# FPGA.net
KiCad netlist of a schematic drawn in Altium Designer
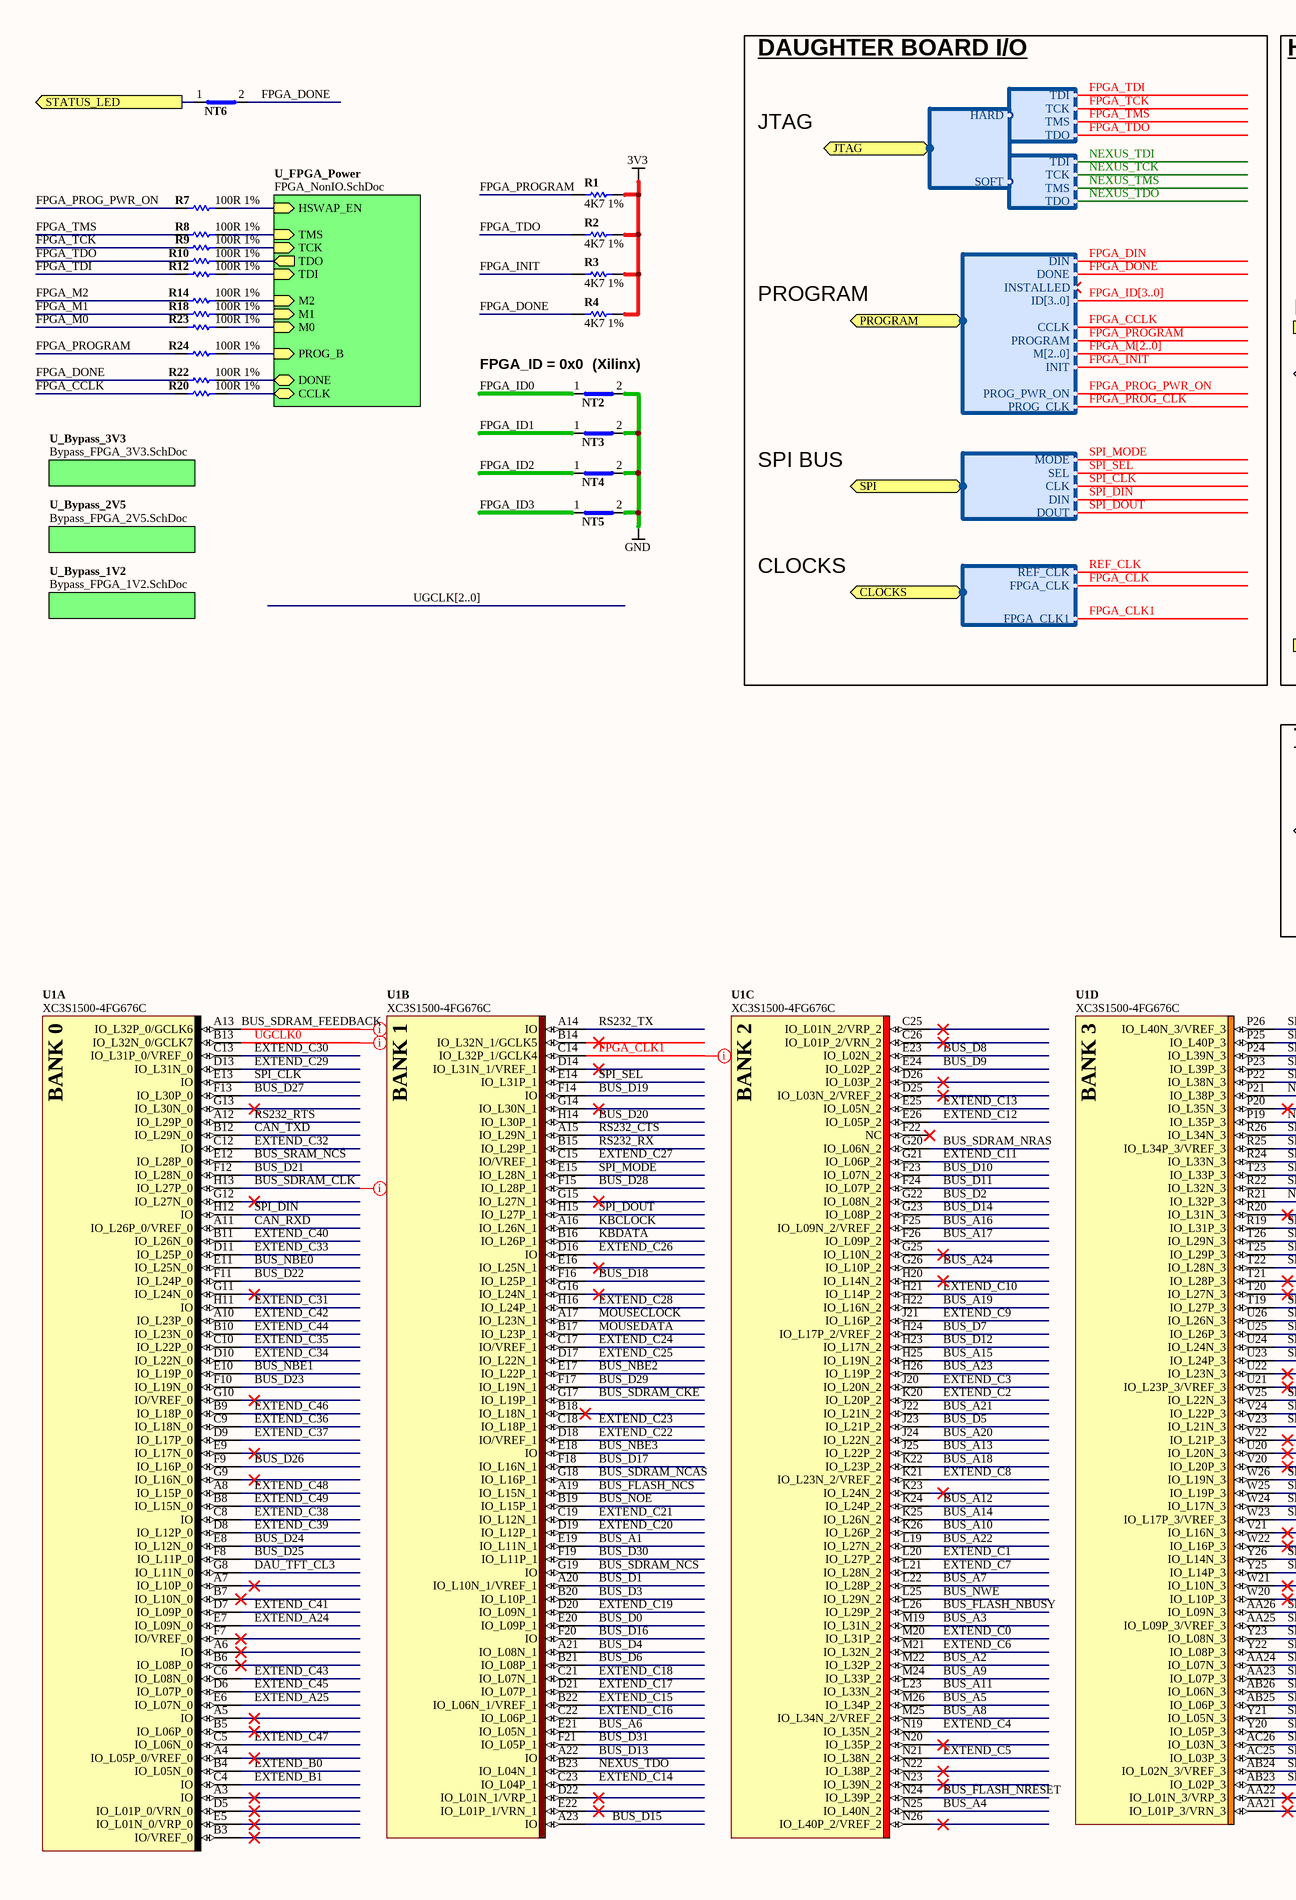
[diagram p0: FPGA.SCHDOC, left]
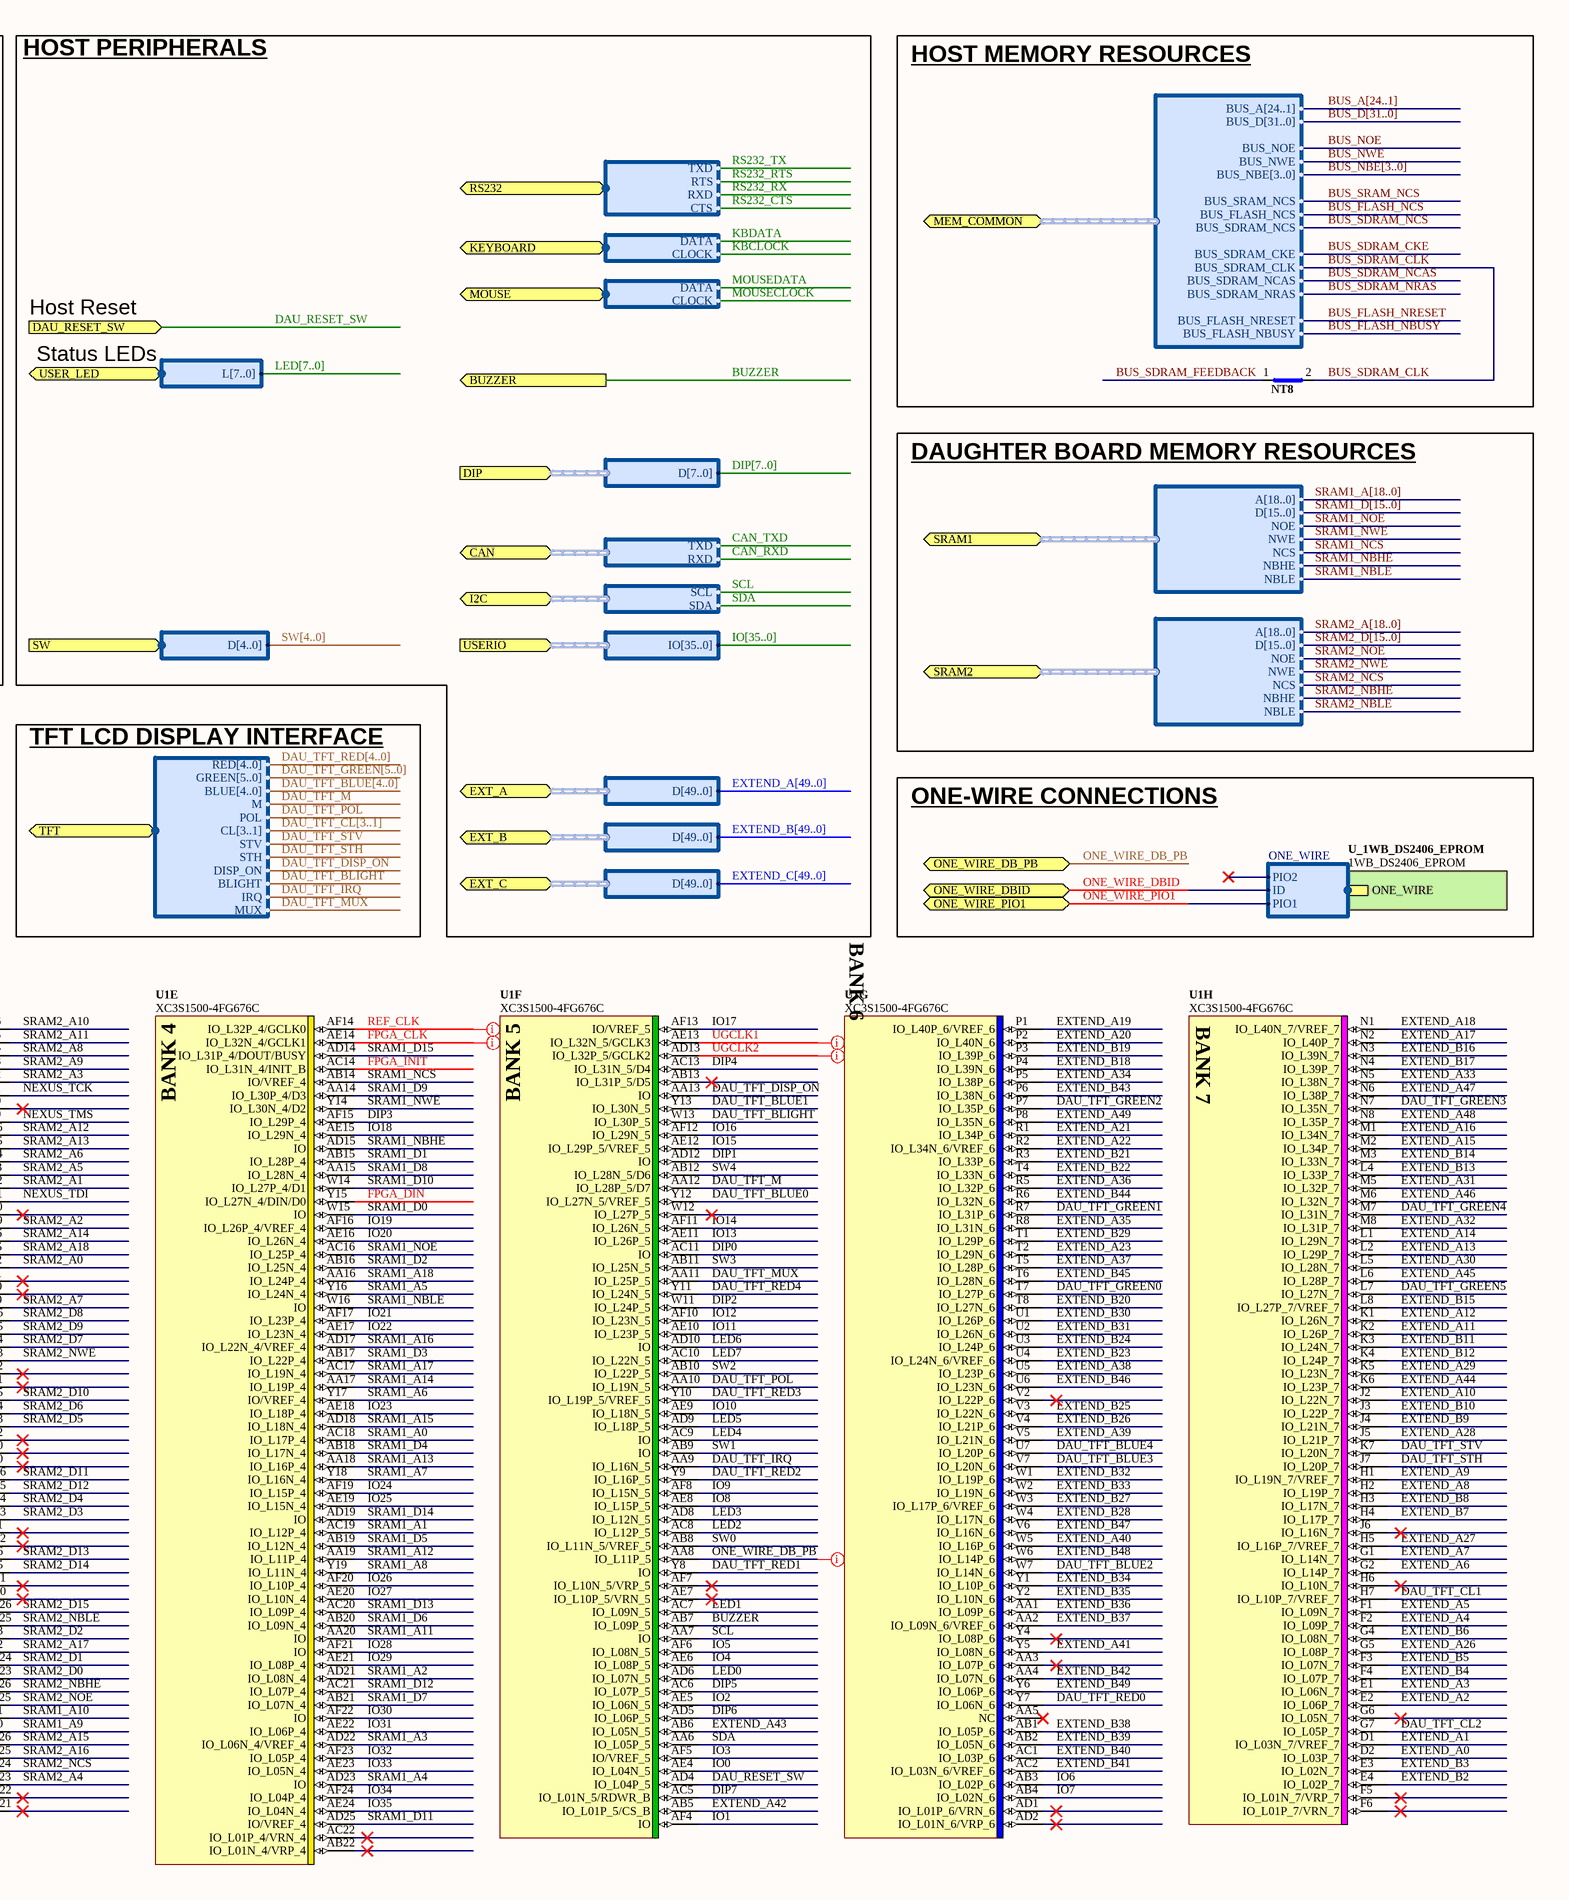
[diagram p1: FPGA.SCHDOC, right]

(export (version "E")
  (design (tool "Eeschema 10.0.6"))
  (components
    (comp (ref "NT2")
      (value "Net Tie SMT2")
      (footprint "NETTIE-SMT2-8X8")
      (description "Net-Tie, Surface Mount, 2 x 0.4mm x 0.2mm SMT Pads - For 0.2mm Track")
      (libsource (lib "AltiumDesignLibrary") (part "NETTIE-SMT2"))
    )
    (comp (ref "NT3")
      (value "Net Tie SMT2")
      (footprint "NETTIE-SMT2-8X8")
      (description "Net-Tie, Surface Mount, 2 x 0.4mm x 0.2mm SMT Pads - For 0.2mm Track")
      (libsource (lib "AltiumDesignLibrary") (part "NETTIE-SMT2"))
    )
    (comp (ref "NT4")
      (value "Net Tie SMT2")
      (footprint "NETTIE-SMT2-8X8")
      (description "Net-Tie, Surface Mount, 2 x 0.4mm x 0.2mm SMT Pads - For 0.2mm Track")
      (libsource (lib "AltiumDesignLibrary") (part "NETTIE-SMT2"))
    )
    (comp (ref "NT5")
      (value "Net Tie SMT2")
      (footprint "NETTIE-SMT2-8X8")
      (description "Net-Tie, Surface Mount, 2 x 0.4mm x 0.2mm SMT Pads - For 0.2mm Track")
      (libsource (lib "AltiumDesignLibrary") (part "NETTIE-SMT2"))
    )
    (comp (ref "NT6")
      (value "Net Tie SMT2")
      (footprint "NETTIE-SMT2-8X8")
      (description "Net-Tie, Surface Mount, 2 x 0.4mm x 0.2mm SMT Pads - For 0.2mm Track")
      (libsource (lib "AltiumDesignLibrary") (part "NETTIE-SMT2"))
    )
    (comp (ref "NT8")
      (value "Net Tie SMT2")
      (footprint "NETTIE-SMT2-8X8")
      (description "Net-Tie, Surface Mount, 2 x 0.4mm x 0.2mm SMT Pads - For 0.2mm Track")
      (libsource (lib "AltiumDesignLibrary") (part "NETTIE-SMT2"))
    )
    (comp (ref "R1")
      (value "4K7 1%")
      (footprint "RESC1005-STAR")
      (description "Resistor, 4K7 1% 0402 (1005)")
      (fields (field (name "TOLERANCE") "1 %"))
      (libsource (lib "AltiumDesignLibrary") (part "RES"))
    )
    (comp (ref "R2")
      (value "4K7 1%")
      (footprint "RESC1005-STAR")
      (description "Resistor, 4K7 1% 0402 (1005)")
      (fields (field (name "TOLERANCE") "1 %"))
      (libsource (lib "AltiumDesignLibrary") (part "RES"))
    )
    (comp (ref "R3")
      (value "4K7 1%")
      (footprint "RESC1005-STAR")
      (description "Resistor, 4K7 1% 0402 (1005)")
      (fields (field (name "TOLERANCE") "1 %"))
      (libsource (lib "AltiumDesignLibrary") (part "RES"))
    )
    (comp (ref "R4")
      (value "4K7 1%")
      (footprint "RESC1005-STAR")
      (description "Resistor, 4K7 1% 0402 (1005)")
      (fields (field (name "TOLERANCE") "1 %"))
      (libsource (lib "AltiumDesignLibrary") (part "RES"))
    )
    (comp (ref "R7")
      (value "100R 1%")
      (footprint "RESC1005-STAR")
      (description "Resistor, 100R 1% 0402 (1005)")
      (fields (field (name "TOLERANCE") "1 %"))
      (libsource (lib "AltiumDesignLibrary") (part "RES"))
    )
    (comp (ref "R8")
      (value "100R 1%")
      (footprint "RESC1005-STAR")
      (description "Resistor, 100R 1% 0402 (1005)")
      (fields (field (name "TOLERANCE") "1 %"))
      (libsource (lib "AltiumDesignLibrary") (part "RES"))
    )
    (comp (ref "R9")
      (value "100R 1%")
      (footprint "RESC1005-STAR")
      (description "Resistor, 100R 1% 0402 (1005)")
      (fields (field (name "TOLERANCE") "1 %"))
      (libsource (lib "AltiumDesignLibrary") (part "RES"))
    )
    (comp (ref "R10")
      (value "100R 1%")
      (footprint "RESC1005-STAR")
      (description "Resistor, 100R 1% 0402 (1005)")
      (fields (field (name "TOLERANCE") "1 %"))
      (libsource (lib "AltiumDesignLibrary") (part "RES"))
    )
    (comp (ref "R12")
      (value "100R 1%")
      (footprint "RESC1005-STAR")
      (description "Resistor, 100R 1% 0402 (1005)")
      (fields (field (name "TOLERANCE") "1 %"))
      (libsource (lib "AltiumDesignLibrary") (part "RES"))
    )
    (comp (ref "R14")
      (value "100R 1%")
      (footprint "RESC1005-STAR")
      (description "Resistor, 100R 1% 0402 (1005)")
      (fields (field (name "TOLERANCE") "1 %"))
      (libsource (lib "AltiumDesignLibrary") (part "RES"))
    )
    (comp (ref "R18")
      (value "100R 1%")
      (footprint "RESC1005-STAR")
      (description "Resistor, 100R 1% 0402 (1005)")
      (fields (field (name "TOLERANCE") "1 %"))
      (libsource (lib "AltiumDesignLibrary") (part "RES"))
    )
    (comp (ref "R20")
      (value "100R 1%")
      (footprint "RESC1005-STAR")
      (description "Resistor, 100R 1% 0402 (1005)")
      (fields (field (name "TOLERANCE") "1 %"))
      (libsource (lib "AltiumDesignLibrary") (part "RES"))
    )
    (comp (ref "R22")
      (value "100R 1%")
      (footprint "RESC1005-STAR")
      (description "Resistor, 100R 1% 0402 (1005)")
      (fields (field (name "TOLERANCE") "1 %"))
      (libsource (lib "AltiumDesignLibrary") (part "RES"))
    )
    (comp (ref "R23")
      (value "100R 1%")
      (footprint "RESC1005-STAR")
      (description "Resistor, 100R 1% 0402 (1005)")
      (fields (field (name "TOLERANCE") "1 %"))
      (libsource (lib "AltiumDesignLibrary") (part "RES"))
    )
    (comp (ref "R24")
      (value "100R 1%")
      (footprint "RESC1005-STAR")
      (description "Resistor, 100R 1% 0402 (1005)")
      (fields (field (name "TOLERANCE") "1 %"))
      (libsource (lib "AltiumDesignLibrary") (part "RES"))
    )
    (comp (ref "U1")
      (value "XC3S1500-4FG676C")
      (footprint "BGA100P26X26-676")
      (description "FPGA, Xilinx Spartan3-1500 FG676 Speed=4")
      (libsource (lib "AltiumDesignLibrary") (part "XC3S1500-4FG676C"))
    )
  )
  (nets
    (net (code "18") (name "/BUS_A1") (class "Default")
      (node (ref "U1") (pin "E19") (pinfunction "IO_L11N_1_E19") (pintype "bidirectional"))
    )
    (net (code "19") (name "/BUS_A2") (class "Default")
      (node (ref "U1") (pin "M22") (pinfunction "IO_L32P_2_M22") (pintype "bidirectional"))
    )
    (net (code "20") (name "/BUS_A3") (class "Default")
      (node (ref "U1") (pin "M19") (pinfunction "IO_L31N_2_M19") (pintype "bidirectional"))
    )
    (net (code "21") (name "/BUS_A4") (class "Default")
      (node (ref "U1") (pin "N25") (pinfunction "IO_L40N_2_N25") (pintype "bidirectional"))
    )
    (net (code "22") (name "/BUS_A5") (class "Default")
      (node (ref "U1") (pin "M26") (pinfunction "IO_L34P_2_M26") (pintype "bidirectional"))
    )
    (net (code "23") (name "/BUS_A6") (class "Default")
      (node (ref "U1") (pin "E21") (pinfunction "IO_L05N_1_E21") (pintype "bidirectional"))
    )
    (net (code "24") (name "/BUS_A7") (class "Default")
      (node (ref "U1") (pin "L22") (pinfunction "IO_L28P_2_L22") (pintype "bidirectional"))
    )
    (net (code "25") (name "/BUS_A8") (class "Default")
      (node (ref "U1") (pin "M25") (pinfunction "IO_L34N_2/VREF_2_M25") (pintype "bidirectional"))
    )
    (net (code "26") (name "/BUS_A9") (class "Default")
      (node (ref "U1") (pin "M24") (pinfunction "IO_L33P_2_M24") (pintype "bidirectional"))
    )
    (net (code "27") (name "/BUS_A10") (class "Default")
      (node (ref "U1") (pin "K26") (pinfunction "IO_L26P_2_K26") (pintype "bidirectional"))
    )
    (net (code "28") (name "/BUS_A11") (class "Default")
      (node (ref "U1") (pin "L23") (pinfunction "IO_L33N_2_L23") (pintype "bidirectional"))
    )
    (net (code "29") (name "/BUS_A12") (class "Default")
      (node (ref "U1") (pin "K24") (pinfunction "IO_L24P_2_K24") (pintype "bidirectional"))
    )
    (net (code "30") (name "/BUS_A13") (class "Default")
      (node (ref "U1") (pin "J25") (pinfunction "IO_L22P_2_J25") (pintype "bidirectional"))
    )
    (net (code "31") (name "/BUS_A14") (class "Default")
      (node (ref "U1") (pin "K25") (pinfunction "IO_L26N_2_K25") (pintype "bidirectional"))
    )
    (net (code "32") (name "/BUS_A15") (class "Default")
      (node (ref "U1") (pin "H25") (pinfunction "IO_L19N_2_H25") (pintype "bidirectional"))
    )
    (net (code "33") (name "/BUS_A16") (class "Default")
      (node (ref "U1") (pin "F25") (pinfunction "IO_L09N_2/VREF_2_F25") (pintype "bidirectional"))
    )
    (net (code "34") (name "/BUS_A17") (class "Default")
      (node (ref "U1") (pin "F26") (pinfunction "IO_L09P_2_F26") (pintype "bidirectional"))
    )
    (net (code "35") (name "/BUS_A18") (class "Default")
      (node (ref "U1") (pin "K22") (pinfunction "IO_L23P_2_K22") (pintype "bidirectional"))
    )
    (net (code "36") (name "/BUS_A19") (class "Default")
      (node (ref "U1") (pin "H22") (pinfunction "IO_L16N_2_H22") (pintype "bidirectional"))
    )
    (net (code "37") (name "/BUS_A20") (class "Default")
      (node (ref "U1") (pin "J24") (pinfunction "IO_L22N_2_J24") (pintype "bidirectional"))
    )
    (net (code "38") (name "/BUS_A21") (class "Default")
      (node (ref "U1") (pin "J22") (pinfunction "IO_L21N_2_J22") (pintype "bidirectional"))
    )
    (net (code "39") (name "/BUS_A22") (class "Default")
      (node (ref "U1") (pin "L19") (pinfunction "IO_L27N_2_L19") (pintype "bidirectional"))
    )
    (net (code "40") (name "/BUS_A23") (class "Default")
      (node (ref "U1") (pin "H26") (pinfunction "IO_L19P_2_H26") (pintype "bidirectional"))
    )
    (net (code "41") (name "/BUS_A24") (class "Default")
      (node (ref "U1") (pin "G26") (pinfunction "IO_L10P_2_G26") (pintype "bidirectional"))
    )
    (net (code "43") (name "/BUS_D0") (class "Default")
      (node (ref "U1") (pin "E20") (pinfunction "IO_L09P_1_E20") (pintype "bidirectional"))
    )
    (net (code "44") (name "/BUS_D1") (class "Default")
      (node (ref "U1") (pin "A20") (pinfunction "IO_L10N_1/VREF_1_A20") (pintype "bidirectional"))
    )
    (net (code "45") (name "/BUS_D2") (class "Default")
      (node (ref "U1") (pin "G22") (pinfunction "IO_L08N_2_G22") (pintype "bidirectional"))
    )
    (net (code "46") (name "/BUS_D3") (class "Default")
      (node (ref "U1") (pin "B20") (pinfunction "IO_L10P_1_B20") (pintype "bidirectional"))
    )
    (net (code "47") (name "/BUS_D4") (class "Default")
      (node (ref "U1") (pin "A21") (pinfunction "IO_L08N_1_A21") (pintype "bidirectional"))
    )
    (net (code "48") (name "/BUS_D5") (class "Default")
      (node (ref "U1") (pin "J23") (pinfunction "IO_L21P_2_J23") (pintype "bidirectional"))
    )
    (net (code "49") (name "/BUS_D6") (class "Default")
      (node (ref "U1") (pin "B21") (pinfunction "IO_L08P_1_B21") (pintype "bidirectional"))
    )
    (net (code "50") (name "/BUS_D7") (class "Default")
      (node (ref "U1") (pin "H24") (pinfunction "IO_L17P_2/VREF_2_H24") (pintype "bidirectional"))
    )
    (net (code "51") (name "/BUS_D8") (class "Default")
      (node (ref "U1") (pin "E23") (pinfunction "IO_L02N_2_E23") (pintype "bidirectional"))
    )
    (net (code "52") (name "/BUS_D9") (class "Default")
      (node (ref "U1") (pin "E24") (pinfunction "IO_L02P_2_E24") (pintype "bidirectional"))
    )
    (net (code "53") (name "/BUS_D10") (class "Default")
      (node (ref "U1") (pin "F23") (pinfunction "IO_L07N_2_F23") (pintype "bidirectional"))
    )
    (net (code "54") (name "/BUS_D11") (class "Default")
      (node (ref "U1") (pin "F24") (pinfunction "IO_L07P_2_F24") (pintype "bidirectional"))
    )
    (net (code "55") (name "/BUS_D12") (class "Default")
      (node (ref "U1") (pin "H23") (pinfunction "IO_L17N_2_H23") (pintype "bidirectional"))
    )
    (net (code "56") (name "/BUS_D13") (class "Default")
      (node (ref "U1") (pin "A22") (pinfunction "IO_A22") (pintype "bidirectional"))
    )
    (net (code "57") (name "/BUS_D14") (class "Default")
      (node (ref "U1") (pin "G23") (pinfunction "IO_L08P_2_G23") (pintype "bidirectional"))
    )
    (net (code "58") (name "/BUS_D15") (class "Default")
      (node (ref "U1") (pin "A23") (pinfunction "IO_A23") (pintype "bidirectional"))
    )
    (net (code "59") (name "/BUS_D16") (class "Default")
      (node (ref "U1") (pin "F20") (pinfunction "IO_F20") (pintype "bidirectional"))
    )
    (net (code "60") (name "/BUS_D17") (class "Default")
      (node (ref "U1") (pin "F18") (pinfunction "IO_L16N_1_F18") (pintype "bidirectional"))
    )
    (net (code "61") (name "/BUS_D18") (class "Default")
      (node (ref "U1") (pin "F16") (pinfunction "IO_L25P_1_F16") (pintype "bidirectional"))
    )
    (net (code "62") (name "/BUS_D19") (class "Default")
      (node (ref "U1") (pin "F14") (pinfunction "IO_F14") (pintype "bidirectional"))
    )
    (net (code "63") (name "/BUS_D20") (class "Default")
      (node (ref "U1") (pin "H14") (pinfunction "IO_L30P_1_H14") (pintype "bidirectional"))
    )
    (net (code "64") (name "/BUS_D21") (class "Default")
      (node (ref "U1") (pin "F12") (pinfunction "IO_L28N_0_F12") (pintype "bidirectional"))
    )
    (net (code "65") (name "/BUS_D22") (class "Default")
      (node (ref "U1") (pin "F11") (pinfunction "IO_L24P_0_F11") (pintype "bidirectional"))
    )
    (net (code "66") (name "/BUS_D23") (class "Default")
      (node (ref "U1") (pin "F10") (pinfunction "IO_L19N_0_F10") (pintype "bidirectional"))
    )
    (net (code "67") (name "/BUS_D24") (class "Default")
      (node (ref "U1") (pin "E8") (pinfunction "IO_L12N_0_E8") (pintype "bidirectional"))
    )
    (net (code "68") (name "/BUS_D25") (class "Default")
      (node (ref "U1") (pin "F8") (pinfunction "IO_L11P_0_F8") (pintype "bidirectional"))
    )
    (net (code "69") (name "/BUS_D26") (class "Default")
      (node (ref "U1") (pin "F9") (pinfunction "IO_L16P_0_F9") (pintype "bidirectional"))
    )
    (net (code "70") (name "/BUS_D27") (class "Default")
      (node (ref "U1") (pin "F13") (pinfunction "IO_L30P_0_F13") (pintype "bidirectional"))
    )
    (net (code "71") (name "/BUS_D28") (class "Default")
      (node (ref "U1") (pin "F15") (pinfunction "IO_L28P_1_F15") (pintype "bidirectional"))
    )
    (net (code "72") (name "/BUS_D29") (class "Default")
      (node (ref "U1") (pin "F17") (pinfunction "IO_L19N_1_F17") (pintype "bidirectional"))
    )
    (net (code "73") (name "/BUS_D30") (class "Default")
      (node (ref "U1") (pin "F19") (pinfunction "IO_L11P_1_F19") (pintype "bidirectional"))
    )
    (net (code "74") (name "/BUS_D31") (class "Default")
      (node (ref "U1") (pin "F21") (pinfunction "IO_L05P_1_F21") (pintype "bidirectional"))
    )
    (net (code "76") (name "/BUS_FLASH_NBUSY") (class "Default")
      (node (ref "U1") (pin "L26") (pinfunction "IO_L29P_2_L26") (pintype "bidirectional"))
    )
    (net (code "77") (name "/BUS_FLASH_NCS") (class "Default")
      (node (ref "U1") (pin "A19") (pinfunction "IO_L15N_1_A19") (pintype "bidirectional"))
    )
    (net (code "78") (name "/BUS_FLASH_NRESET") (class "Default")
      (node (ref "U1") (pin "N24") (pinfunction "IO_L39P_2_N24") (pintype "bidirectional"))
    )
    (net (code "79") (name "/BUS_NBE0") (class "Default")
      (node (ref "U1") (pin "E11") (pinfunction "IO_L25N_0_E11") (pintype "bidirectional"))
    )
    (net (code "80") (name "/BUS_NBE1") (class "Default")
      (node (ref "U1") (pin "E10") (pinfunction "IO_L19P_0_E10") (pintype "bidirectional"))
    )
    (net (code "81") (name "/BUS_NBE2") (class "Default")
      (node (ref "U1") (pin "E17") (pinfunction "IO_L22P_1_E17") (pintype "bidirectional"))
    )
    (net (code "82") (name "/BUS_NBE3") (class "Default")
      (node (ref "U1") (pin "E18") (pinfunction "IO_E18") (pintype "bidirectional"))
    )
    (net (code "84") (name "/BUS_NOE") (class "Default")
      (node (ref "U1") (pin "B19") (pinfunction "IO_L15P_1_B19") (pintype "bidirectional"))
    )
    (net (code "85") (name "/BUS_NWE") (class "Default")
      (node (ref "U1") (pin "L25") (pinfunction "IO_L29N_2_L25") (pintype "bidirectional"))
    )
    (net (code "86") (name "/BUS_SDRAM_CKE") (class "Default")
      (node (ref "U1") (pin "G17") (pinfunction "IO_L19P_1_G17") (pintype "bidirectional"))
    )
    (net (code "87") (name "/BUS_SDRAM_CLK") (class "Default")
      (node (ref "NT8") (pin "2") (pinfunction "Net2_2") (pintype "passive"))
      (node (ref "U1") (pin "H13") (pinfunction "IO_L27P_0_H13") (pintype "bidirectional"))
    )
    (net (code "88") (name "/BUS_SDRAM_FEEDBACK") (class "Default")
      (node (ref "NT8") (pin "1") (pinfunction "Net1_1") (pintype "passive"))
      (node (ref "U1") (pin "A13") (pinfunction "IO_L32P_0/GCLK6_A13") (pintype "bidirectional"))
    )
    (net (code "89") (name "/BUS_SDRAM_NCAS") (class "Default")
      (node (ref "U1") (pin "G18") (pinfunction "IO_L16P_1_G18") (pintype "bidirectional"))
    )
    (net (code "90") (name "/BUS_SDRAM_NCS") (class "Default")
      (node (ref "U1") (pin "G19") (pinfunction "IO_G19") (pintype "bidirectional"))
    )
    (net (code "91") (name "/BUS_SDRAM_NRAS") (class "Default")
      (node (ref "U1") (pin "G20") (pinfunction "IO_L06N_2_G20") (pintype "bidirectional"))
    )
    (net (code "92") (name "/BUS_SRAM_NCS") (class "Default")
      (node (ref "U1") (pin "E12") (pinfunction "IO_L28P_0_E12") (pintype "bidirectional"))
    )
    (net (code "93") (name "/BUZZER") (class "Default")
      (node (ref "U1") (pin "AB7") (pinfunction "IO_L09P_5_AB7") (pintype "bidirectional"))
    )
    (net (code "94") (name "/CAN_RXD") (class "Default")
      (node (ref "U1") (pin "A11") (pinfunction "IO_L26P_0/VREF_0_A11") (pintype "bidirectional"))
    )
    (net (code "95") (name "/CAN_TXD") (class "Default")
      (node (ref "U1") (pin "B12") (pinfunction "IO_L29N_0_B12") (pintype "bidirectional"))
    )
    (net (code "96") (name "/CCLK") (class "Default")
      (node (ref "R20") (pin "2") (pinfunction "2_2") (pintype "passive"))
    )
    (net (code "97") (name "/DAU_RESET_SW") (class "Default")
      (node (ref "U1") (pin "AD4") (pinfunction "IO_L04P_5_AD4") (pintype "bidirectional"))
    )
    (net (code "98") (name "/DAU_TFT_BLIGHT") (class "Default")
      (node (ref "U1") (pin "W13") (pinfunction "IO_L30P_5_W13") (pintype "bidirectional"))
    )
    (net (code "99") (name "/DAU_TFT_BLUE0") (class "Default")
      (node (ref "U1") (pin "Y12") (pinfunction "IO_L27N_5/VREF_5_Y12") (pintype "bidirectional"))
    )
    (net (code "100") (name "/DAU_TFT_BLUE1") (class "Default")
      (node (ref "U1") (pin "Y13") (pinfunction "IO_L30N_5_Y13") (pintype "bidirectional"))
    )
    (net (code "101") (name "/DAU_TFT_BLUE2") (class "Default")
      (node (ref "U1") (pin "W7") (pinfunction "IO_L14N_6_W7") (pintype "bidirectional"))
    )
    (net (code "102") (name "/DAU_TFT_BLUE3") (class "Default")
      (node (ref "U1") (pin "V7") (pinfunction "IO_L20N_6_V7") (pintype "bidirectional"))
    )
    (net (code "103") (name "/DAU_TFT_BLUE4") (class "Default")
      (node (ref "U1") (pin "U7") (pinfunction "IO_L20P_6_U7") (pintype "bidirectional"))
    )
    (net (code "105") (name "/DAU_TFT_CL1") (class "Default")
      (node (ref "U1") (pin "H7") (pinfunction "IO_L10P_7/VREF_7_H7") (pintype "bidirectional"))
    )
    (net (code "106") (name "/DAU_TFT_CL2") (class "Default")
      (node (ref "U1") (pin "G7") (pinfunction "IO_L05P_7_G7") (pintype "bidirectional"))
    )
    (net (code "107") (name "/DAU_TFT_CL3") (class "Default")
      (node (ref "U1") (pin "G8") (pinfunction "IO_L11N_0_G8") (pintype "bidirectional"))
    )
    (net (code "108") (name "/DAU_TFT_DISP_ON") (class "Default")
      (node (ref "U1") (pin "AA13") (pinfunction "IO_AA13") (pintype "bidirectional"))
    )
    (net (code "109") (name "/DAU_TFT_GREEN0") (class "Default")
      (node (ref "U1") (pin "T7") (pinfunction "IO_L27P_6_T7") (pintype "bidirectional"))
    )
    (net (code "110") (name "/DAU_TFT_GREEN1") (class "Default")
      (node (ref "U1") (pin "R7") (pinfunction "IO_L31P_6_R7") (pintype "bidirectional"))
    )
    (net (code "111") (name "/DAU_TFT_GREEN2") (class "Default")
      (node (ref "U1") (pin "P7") (pinfunction "IO_L35P_6_P7") (pintype "bidirectional"))
    )
    (net (code "112") (name "/DAU_TFT_GREEN3") (class "Default")
      (node (ref "U1") (pin "N7") (pinfunction "IO_L35N_7_N7") (pintype "bidirectional"))
    )
    (net (code "113") (name "/DAU_TFT_GREEN4") (class "Default")
      (node (ref "U1") (pin "M7") (pinfunction "IO_L31N_7_M7") (pintype "bidirectional"))
    )
    (net (code "114") (name "/DAU_TFT_GREEN5") (class "Default")
      (node (ref "U1") (pin "L7") (pinfunction "IO_L27N_7_L7") (pintype "bidirectional"))
    )
    (net (code "116") (name "/DAU_TFT_IRQ") (class "Default")
      (node (ref "U1") (pin "AA9") (pinfunction "IO_L16N_5_AA9") (pintype "bidirectional"))
    )
    (net (code "117") (name "/DAU_TFT_M") (class "Default")
      (node (ref "U1") (pin "AA12") (pinfunction "IO_L28P_5/D7_AA12") (pintype "bidirectional"))
    )
    (net (code "118") (name "/DAU_TFT_MUX") (class "Default")
      (node (ref "U1") (pin "AA11") (pinfunction "IO_L25P_5_AA11") (pintype "bidirectional"))
    )
    (net (code "119") (name "/DAU_TFT_POL") (class "Default")
      (node (ref "U1") (pin "AA10") (pinfunction "IO_L19N_5_AA10") (pintype "bidirectional"))
    )
    (net (code "120") (name "/DAU_TFT_RED0") (class "Default")
      (node (ref "U1") (pin "Y7") (pinfunction "IO_L06N_6_Y7") (pintype "bidirectional"))
    )
    (net (code "121") (name "/DAU_TFT_RED1") (class "Default")
      (node (ref "U1") (pin "Y8") (pinfunction "IO_Y8") (pintype "bidirectional"))
    )
    (net (code "122") (name "/DAU_TFT_RED2") (class "Default")
      (node (ref "U1") (pin "Y9") (pinfunction "IO_L16P_5_Y9") (pintype "bidirectional"))
    )
    (net (code "123") (name "/DAU_TFT_RED3") (class "Default")
      (node (ref "U1") (pin "Y10") (pinfunction "IO_L19P_5/VREF_5_Y10") (pintype "bidirectional"))
    )
    (net (code "124") (name "/DAU_TFT_RED4") (class "Default")
      (node (ref "U1") (pin "Y11") (pinfunction "IO_L24N_5_Y11") (pintype "bidirectional"))
    )
    (net (code "126") (name "/DAU_TFT_STH") (class "Default")
      (node (ref "U1") (pin "J7") (pinfunction "IO_L20P_7_J7") (pintype "bidirectional"))
    )
    (net (code "127") (name "/DAU_TFT_STV") (class "Default")
      (node (ref "U1") (pin "K7") (pinfunction "IO_L20N_7_K7") (pintype "bidirectional"))
    )
    (net (code "128") (name "/DIP0") (class "Default")
      (node (ref "U1") (pin "AC11") (pinfunction "IO_AC11") (pintype "bidirectional"))
    )
    (net (code "129") (name "/DIP1") (class "Default")
      (node (ref "U1") (pin "AD12") (pinfunction "IO_AD12") (pintype "bidirectional"))
    )
    (net (code "130") (name "/DIP2") (class "Default")
      (node (ref "U1") (pin "W11") (pinfunction "IO_L24P_5_W11") (pintype "bidirectional"))
    )
    (net (code "131") (name "/DIP3") (class "Default")
      (node (ref "U1") (pin "AF15") (pinfunction "IO_L29P_4_AF15") (pintype "bidirectional"))
    )
    (net (code "132") (name "/DIP4") (class "Default")
      (node (ref "U1") (pin "AC13") (pinfunction "IO_L31N_5/D4_AC13") (pintype "bidirectional"))
    )
    (net (code "133") (name "/DIP5") (class "Default")
      (node (ref "U1") (pin "AC6") (pinfunction "IO_L07P_5_AC6") (pintype "bidirectional"))
    )
    (net (code "134") (name "/DIP6") (class "Default")
      (node (ref "U1") (pin "AD5") (pinfunction "IO_L06P_5_AD5") (pintype "bidirectional"))
    )
    (net (code "135") (name "/DIP7") (class "Default")
      (node (ref "U1") (pin "AC5") (pinfunction "IO_L01N_5/RDWR_B_AC5") (pintype "bidirectional"))
    )
    (net (code "137") (name "/DONE") (class "Default")
      (node (ref "R22") (pin "2") (pinfunction "2_2") (pintype "passive"))
    )
    (net (code "138") (name "/EXTEND_A0") (class "Default")
      (node (ref "U1") (pin "D2") (pinfunction "IO_L03P_7_D2") (pintype "bidirectional"))
    )
    (net (code "139") (name "/EXTEND_A1") (class "Default")
      (node (ref "U1") (pin "D1") (pinfunction "IO_L03N_7/VREF_7_D1") (pintype "bidirectional"))
    )
    (net (code "140") (name "/EXTEND_A2") (class "Default")
      (node (ref "U1") (pin "E2") (pinfunction "IO_L06P_7_E2") (pintype "bidirectional"))
    )
    (net (code "141") (name "/EXTEND_A3") (class "Default")
      (node (ref "U1") (pin "E1") (pinfunction "IO_L06N_7_E1") (pintype "bidirectional"))
    )
    (net (code "142") (name "/EXTEND_A4") (class "Default")
      (node (ref "U1") (pin "F2") (pinfunction "IO_L09P_7_F2") (pintype "bidirectional"))
    )
    (net (code "143") (name "/EXTEND_A5") (class "Default")
      (node (ref "U1") (pin "F1") (pinfunction "IO_L09N_7_F1") (pintype "bidirectional"))
    )
    (net (code "144") (name "/EXTEND_A6") (class "Default")
      (node (ref "U1") (pin "G2") (pinfunction "IO_L14P_7_G2") (pintype "bidirectional"))
    )
    (net (code "145") (name "/EXTEND_A7") (class "Default")
      (node (ref "U1") (pin "G1") (pinfunction "IO_L14N_7_G1") (pintype "bidirectional"))
    )
    (net (code "146") (name "/EXTEND_A8") (class "Default")
      (node (ref "U1") (pin "H2") (pinfunction "IO_L19P_7_H2") (pintype "bidirectional"))
    )
    (net (code "147") (name "/EXTEND_A9") (class "Default")
      (node (ref "U1") (pin "H1") (pinfunction "IO_L19N_7/VREF_7_H1") (pintype "bidirectional"))
    )
    (net (code "148") (name "/EXTEND_A10") (class "Default")
      (node (ref "U1") (pin "J2") (pinfunction "IO_L22N_7_J2") (pintype "bidirectional"))
    )
    (net (code "149") (name "/EXTEND_A11") (class "Default")
      (node (ref "U1") (pin "K2") (pinfunction "IO_L26P_7_K2") (pintype "bidirectional"))
    )
    (net (code "150") (name "/EXTEND_A12") (class "Default")
      (node (ref "U1") (pin "K1") (pinfunction "IO_L26N_7_K1") (pintype "bidirectional"))
    )
    (net (code "151") (name "/EXTEND_A13") (class "Default")
      (node (ref "U1") (pin "L2") (pinfunction "IO_L29P_7_L2") (pintype "bidirectional"))
    )
    (net (code "152") (name "/EXTEND_A14") (class "Default")
      (node (ref "U1") (pin "L1") (pinfunction "IO_L29N_7_L1") (pintype "bidirectional"))
    )
    (net (code "153") (name "/EXTEND_A15") (class "Default")
      (node (ref "U1") (pin "M2") (pinfunction "IO_L34P_7_M2") (pintype "bidirectional"))
    )
    (net (code "154") (name "/EXTEND_A16") (class "Default")
      (node (ref "U1") (pin "M1") (pinfunction "IO_L34N_7_M1") (pintype "bidirectional"))
    )
    (net (code "155") (name "/EXTEND_A17") (class "Default")
      (node (ref "U1") (pin "N2") (pinfunction "IO_L40P_7_N2") (pintype "bidirectional"))
    )
    (net (code "156") (name "/EXTEND_A18") (class "Default")
      (node (ref "U1") (pin "N1") (pinfunction "IO_L40N_7/VREF_7_N1") (pintype "bidirectional"))
    )
    (net (code "157") (name "/EXTEND_A19") (class "Default")
      (node (ref "U1") (pin "P1") (pinfunction "IO_L40P_6/VREF_6_P1") (pintype "bidirectional"))
    )
    (net (code "158") (name "/EXTEND_A20") (class "Default")
      (node (ref "U1") (pin "P2") (pinfunction "IO_L40N_6_P2") (pintype "bidirectional"))
    )
    (net (code "159") (name "/EXTEND_A21") (class "Default")
      (node (ref "U1") (pin "R1") (pinfunction "IO_L34P_6_R1") (pintype "bidirectional"))
    )
    (net (code "160") (name "/EXTEND_A22") (class "Default")
      (node (ref "U1") (pin "R2") (pinfunction "IO_L34N_6/VREF_6_R2") (pintype "bidirectional"))
    )
    (net (code "161") (name "/EXTEND_A23") (class "Default")
      (node (ref "U1") (pin "T2") (pinfunction "IO_L29N_6_T2") (pintype "bidirectional"))
    )
    (net (code "162") (name "/EXTEND_A24") (class "Default")
      (node (ref "U1") (pin "E7") (pinfunction "IO_L09N_0_E7") (pintype "bidirectional"))
    )
    (net (code "163") (name "/EXTEND_A25") (class "Default")
      (node (ref "U1") (pin "E6") (pinfunction "IO_L07N_0_E6") (pintype "bidirectional"))
    )
    (net (code "164") (name "/EXTEND_A26") (class "Default")
      (node (ref "U1") (pin "G5") (pinfunction "IO_L08P_7_G5") (pintype "bidirectional"))
    )
    (net (code "165") (name "/EXTEND_A27") (class "Default")
      (node (ref "U1") (pin "H5") (pinfunction "IO_L16P_7/VREF_7_H5") (pintype "bidirectional"))
    )
    (net (code "166") (name "/EXTEND_A28") (class "Default")
      (node (ref "U1") (pin "J5") (pinfunction "IO_L21P_7_J5") (pintype "bidirectional"))
    )
    (net (code "167") (name "/EXTEND_A29") (class "Default")
      (node (ref "U1") (pin "K5") (pinfunction "IO_L23N_7_K5") (pintype "bidirectional"))
    )
    (net (code "168") (name "/EXTEND_A30") (class "Default")
      (node (ref "U1") (pin "L5") (pinfunction "IO_L28N_7_L5") (pintype "bidirectional"))
    )
    (net (code "169") (name "/EXTEND_A31") (class "Default")
      (node (ref "U1") (pin "M5") (pinfunction "IO_L32P_7_M5") (pintype "bidirectional"))
    )
    (net (code "170") (name "/EXTEND_A32") (class "Default")
      (node (ref "U1") (pin "M8") (pinfunction "IO_L31P_7_M8") (pintype "bidirectional"))
    )
    (net (code "171") (name "/EXTEND_A33") (class "Default")
      (node (ref "U1") (pin "N5") (pinfunction "IO_L38N_7_N5") (pintype "bidirectional"))
    )
    (net (code "172") (name "/EXTEND_A34") (class "Default")
      (node (ref "U1") (pin "P5") (pinfunction "IO_L38P_6_P5") (pintype "bidirectional"))
    )
    (net (code "173") (name "/EXTEND_A35") (class "Default")
      (node (ref "U1") (pin "R8") (pinfunction "IO_L31N_6_R8") (pintype "bidirectional"))
    )
    (net (code "174") (name "/EXTEND_A36") (class "Default")
      (node (ref "U1") (pin "R5") (pinfunction "IO_L32P_6_R5") (pintype "bidirectional"))
    )
    (net (code "175") (name "/EXTEND_A37") (class "Default")
      (node (ref "U1") (pin "T5") (pinfunction "IO_L28P_6_T5") (pintype "bidirectional"))
    )
    (net (code "176") (name "/EXTEND_A38") (class "Default")
      (node (ref "U1") (pin "U5") (pinfunction "IO_L23P_6_U5") (pintype "bidirectional"))
    )
    (net (code "177") (name "/EXTEND_A39") (class "Default")
      (node (ref "U1") (pin "V5") (pinfunction "IO_L21N_6_V5") (pintype "bidirectional"))
    )
    (net (code "178") (name "/EXTEND_A40") (class "Default")
      (node (ref "U1") (pin "W5") (pinfunction "IO_L16P_6_W5") (pintype "bidirectional"))
    )
    (net (code "179") (name "/EXTEND_A41") (class "Default")
      (node (ref "U1") (pin "Y5") (pinfunction "IO_L08N_6_Y5") (pintype "bidirectional"))
    )
    (net (code "180") (name "/EXTEND_A42") (class "Default")
      (node (ref "U1") (pin "AB5") (pinfunction "IO_L01P_5/CS_B_AB5") (pintype "bidirectional"))
    )
    (net (code "181") (name "/EXTEND_A43") (class "Default")
      (node (ref "U1") (pin "AB6") (pinfunction "IO_L05N_5_AB6") (pintype "bidirectional"))
    )
    (net (code "182") (name "/EXTEND_A44") (class "Default")
      (node (ref "U1") (pin "K6") (pinfunction "IO_L23P_7_K6") (pintype "bidirectional"))
    )
    (net (code "183") (name "/EXTEND_A45") (class "Default")
      (node (ref "U1") (pin "L6") (pinfunction "IO_L28P_7_L6") (pintype "bidirectional"))
    )
    (net (code "184") (name "/EXTEND_A46") (class "Default")
      (node (ref "U1") (pin "M6") (pinfunction "IO_L32N_7_M6") (pintype "bidirectional"))
    )
    (net (code "185") (name "/EXTEND_A47") (class "Default")
      (node (ref "U1") (pin "N6") (pinfunction "IO_L38P_7_N6") (pintype "bidirectional"))
    )
    (net (code "186") (name "/EXTEND_A48") (class "Default")
      (node (ref "U1") (pin "N8") (pinfunction "IO_L35P_7_N8") (pintype "bidirectional"))
    )
    (net (code "187") (name "/EXTEND_A49") (class "Default")
      (node (ref "U1") (pin "P8") (pinfunction "IO_L35N_6_P8") (pintype "bidirectional"))
    )
    (net (code "189") (name "/EXTEND_B0") (class "Default")
      (node (ref "U1") (pin "B4") (pinfunction "IO_L05N_0_B4") (pintype "bidirectional"))
    )
    (net (code "190") (name "/EXTEND_B1") (class "Default")
      (node (ref "U1") (pin "C4") (pinfunction "IO_C4") (pintype "bidirectional"))
    )
    (net (code "191") (name "/EXTEND_B2") (class "Default")
      (node (ref "U1") (pin "E4") (pinfunction "IO_L02P_7_E4") (pintype "bidirectional"))
    )
    (net (code "192") (name "/EXTEND_B3") (class "Default")
      (node (ref "U1") (pin "E3") (pinfunction "IO_L02N_7_E3") (pintype "bidirectional"))
    )
    (net (code "193") (name "/EXTEND_B4") (class "Default")
      (node (ref "U1") (pin "F4") (pinfunction "IO_L07P_7_F4") (pintype "bidirectional"))
    )
    (net (code "194") (name "/EXTEND_B5") (class "Default")
      (node (ref "U1") (pin "F3") (pinfunction "IO_L07N_7_F3") (pintype "bidirectional"))
    )
    (net (code "195") (name "/EXTEND_B6") (class "Default")
      (node (ref "U1") (pin "G4") (pinfunction "IO_L08N_7_G4") (pintype "bidirectional"))
    )
    (net (code "196") (name "/EXTEND_B7") (class "Default")
      (node (ref "U1") (pin "H4") (pinfunction "IO_L17P_7_H4") (pintype "bidirectional"))
    )
    (net (code "197") (name "/EXTEND_B8") (class "Default")
      (node (ref "U1") (pin "H3") (pinfunction "IO_L17N_7_H3") (pintype "bidirectional"))
    )
    (net (code "198") (name "/EXTEND_B9") (class "Default")
      (node (ref "U1") (pin "J4") (pinfunction "IO_L21N_7_J4") (pintype "bidirectional"))
    )
    (net (code "199") (name "/EXTEND_B10") (class "Default")
      (node (ref "U1") (pin "J3") (pinfunction "IO_L22P_7_J3") (pintype "bidirectional"))
    )
    (net (code "200") (name "/EXTEND_B11") (class "Default")
      (node (ref "U1") (pin "K3") (pinfunction "IO_L24N_7_K3") (pintype "bidirectional"))
    )
    (net (code "201") (name "/EXTEND_B12") (class "Default")
      (node (ref "U1") (pin "K4") (pinfunction "IO_L24P_7_K4") (pintype "bidirectional"))
    )
    (net (code "202") (name "/EXTEND_B13") (class "Default")
      (node (ref "U1") (pin "L4") (pinfunction "IO_L33P_7_L4") (pintype "bidirectional"))
    )
    (net (code "203") (name "/EXTEND_B14") (class "Default")
      (node (ref "U1") (pin "M3") (pinfunction "IO_L33N_7_M3") (pintype "bidirectional"))
    )
    (net (code "204") (name "/EXTEND_B15") (class "Default")
      (node (ref "U1") (pin "L8") (pinfunction "IO_L27P_7/VREF_7_L8") (pintype "bidirectional"))
    )
    (net (code "205") (name "/EXTEND_B16") (class "Default")
      (node (ref "U1") (pin "N3") (pinfunction "IO_L39N_7_N3") (pintype "bidirectional"))
    )
    (net (code "206") (name "/EXTEND_B17") (class "Default")
      (node (ref "U1") (pin "N4") (pinfunction "IO_L39P_7_N4") (pintype "bidirectional"))
    )
    (net (code "207") (name "/EXTEND_B18") (class "Default")
      (node (ref "U1") (pin "P4") (pinfunction "IO_L39N_6_P4") (pintype "bidirectional"))
    )
    (net (code "208") (name "/EXTEND_B19") (class "Default")
      (node (ref "U1") (pin "P3") (pinfunction "IO_L39P_6_P3") (pintype "bidirectional"))
    )
    (net (code "209") (name "/EXTEND_B20") (class "Default")
      (node (ref "U1") (pin "T8") (pinfunction "IO_L27N_6_T8") (pintype "bidirectional"))
    )
    (net (code "210") (name "/EXTEND_B21") (class "Default")
      (node (ref "U1") (pin "R3") (pinfunction "IO_L33P_6_R3") (pintype "bidirectional"))
    )
    (net (code "211") (name "/EXTEND_B22") (class "Default")
      (node (ref "U1") (pin "T4") (pinfunction "IO_L33N_6_T4") (pintype "bidirectional"))
    )
    (net (code "212") (name "/EXTEND_B23") (class "Default")
      (node (ref "U1") (pin "U4") (pinfunction "IO_L24N_6/VREF_6_U4") (pintype "bidirectional"))
    )
    (net (code "213") (name "/EXTEND_B24") (class "Default")
      (node (ref "U1") (pin "U3") (pinfunction "IO_L24P_6_U3") (pintype "bidirectional"))
    )
    (net (code "214") (name "/EXTEND_B25") (class "Default")
      (node (ref "U1") (pin "V3") (pinfunction "IO_L22N_6_V3") (pintype "bidirectional"))
    )
    (net (code "215") (name "/EXTEND_B26") (class "Default")
      (node (ref "U1") (pin "V4") (pinfunction "IO_L21P_6_V4") (pintype "bidirectional"))
    )
    (net (code "216") (name "/EXTEND_B27") (class "Default")
      (node (ref "U1") (pin "W3") (pinfunction "IO_L17P_6/VREF_6_W3") (pintype "bidirectional"))
    )
    (net (code "217") (name "/EXTEND_B28") (class "Default")
      (node (ref "U1") (pin "W4") (pinfunction "IO_L17N_6_W4") (pintype "bidirectional"))
    )
    (net (code "218") (name "/EXTEND_B29") (class "Default")
      (node (ref "U1") (pin "T1") (pinfunction "IO_L29P_6_T1") (pintype "bidirectional"))
    )
    (net (code "219") (name "/EXTEND_B30") (class "Default")
      (node (ref "U1") (pin "U1") (pinfunction "IO_L26P_6_U1") (pintype "bidirectional"))
    )
    (net (code "220") (name "/EXTEND_B31") (class "Default")
      (node (ref "U1") (pin "U2") (pinfunction "IO_L26N_6_U2") (pintype "bidirectional"))
    )
    (net (code "221") (name "/EXTEND_B32") (class "Default")
      (node (ref "U1") (pin "W1") (pinfunction "IO_L19P_6_W1") (pintype "bidirectional"))
    )
    (net (code "222") (name "/EXTEND_B33") (class "Default")
      (node (ref "U1") (pin "W2") (pinfunction "IO_L19N_6_W2") (pintype "bidirectional"))
    )
    (net (code "223") (name "/EXTEND_B34") (class "Default")
      (node (ref "U1") (pin "Y1") (pinfunction "IO_L10P_6_Y1") (pintype "bidirectional"))
    )
    (net (code "224") (name "/EXTEND_B35") (class "Default")
      (node (ref "U1") (pin "Y2") (pinfunction "IO_L10N_6_Y2") (pintype "bidirectional"))
    )
    (net (code "225") (name "/EXTEND_B36") (class "Default")
      (node (ref "U1") (pin "AA1") (pinfunction "IO_L09P_6_AA1") (pintype "bidirectional"))
    )
    (net (code "226") (name "/EXTEND_B37") (class "Default")
      (node (ref "U1") (pin "AA2") (pinfunction "IO_L09N_6/VREF_6_AA2") (pintype "bidirectional"))
    )
    (net (code "227") (name "/EXTEND_B38") (class "Default")
      (node (ref "U1") (pin "AB1") (pinfunction "IO_L05P_6_AB1") (pintype "bidirectional"))
    )
    (net (code "228") (name "/EXTEND_B39") (class "Default")
      (node (ref "U1") (pin "AB2") (pinfunction "IO_L05N_6_AB2") (pintype "bidirectional"))
    )
    (net (code "229") (name "/EXTEND_B40") (class "Default")
      (node (ref "U1") (pin "AC1") (pinfunction "IO_L03P_6_AC1") (pintype "bidirectional"))
    )
    (net (code "230") (name "/EXTEND_B41") (class "Default")
      (node (ref "U1") (pin "AC2") (pinfunction "IO_L03N_6/VREF_6_AC2") (pintype "bidirectional"))
    )
    (net (code "231") (name "/EXTEND_B42") (class "Default")
      (node (ref "U1") (pin "AA4") (pinfunction "IO_L07N_6_AA4") (pintype "bidirectional"))
    )
    (net (code "232") (name "/EXTEND_B43") (class "Default")
      (node (ref "U1") (pin "P6") (pinfunction "IO_L38N_6_P6") (pintype "bidirectional"))
    )
    (net (code "233") (name "/EXTEND_B44") (class "Default")
      (node (ref "U1") (pin "R6") (pinfunction "IO_L32N_6_R6") (pintype "bidirectional"))
    )
    (net (code "234") (name "/EXTEND_B45") (class "Default")
      (node (ref "U1") (pin "T6") (pinfunction "IO_L28N_6_T6") (pintype "bidirectional"))
    )
    (net (code "235") (name "/EXTEND_B46") (class "Default")
      (node (ref "U1") (pin "U6") (pinfunction "IO_L23N_6_U6") (pintype "bidirectional"))
    )
    (net (code "236") (name "/EXTEND_B47") (class "Default")
      (node (ref "U1") (pin "V6") (pinfunction "IO_L16N_6_V6") (pintype "bidirectional"))
    )
    (net (code "237") (name "/EXTEND_B48") (class "Default")
      (node (ref "U1") (pin "W6") (pinfunction "IO_L14P_6_W6") (pintype "bidirectional"))
    )
    (net (code "238") (name "/EXTEND_B49") (class "Default")
      (node (ref "U1") (pin "Y6") (pinfunction "IO_L06P_6_Y6") (pintype "bidirectional"))
    )
    (net (code "240") (name "/EXTEND_C0") (class "Default")
      (node (ref "U1") (pin "M20") (pinfunction "IO_L31P_2_M20") (pintype "bidirectional"))
    )
    (net (code "241") (name "/EXTEND_C1") (class "Default")
      (node (ref "U1") (pin "L20") (pinfunction "IO_L27P_2_L20") (pintype "bidirectional"))
    )
    (net (code "242") (name "/EXTEND_C2") (class "Default")
      (node (ref "U1") (pin "K20") (pinfunction "IO_L20P_2_K20") (pintype "bidirectional"))
    )
    (net (code "243") (name "/EXTEND_C3") (class "Default")
      (node (ref "U1") (pin "J20") (pinfunction "IO_L20N_2_J20") (pintype "bidirectional"))
    )
    (net (code "244") (name "/EXTEND_C4") (class "Default")
      (node (ref "U1") (pin "N19") (pinfunction "IO_L35N_2_N19") (pintype "bidirectional"))
    )
    (net (code "245") (name "/EXTEND_C5") (class "Default")
      (node (ref "U1") (pin "N21") (pinfunction "IO_L38N_2_N21") (pintype "bidirectional"))
    )
    (net (code "246") (name "/EXTEND_C6") (class "Default")
      (node (ref "U1") (pin "M21") (pinfunction "IO_L32N_2_M21") (pintype "bidirectional"))
    )
    (net (code "247") (name "/EXTEND_C7") (class "Default")
      (node (ref "U1") (pin "L21") (pinfunction "IO_L28N_2_L21") (pintype "bidirectional"))
    )
    (net (code "248") (name "/EXTEND_C8") (class "Default")
      (node (ref "U1") (pin "K21") (pinfunction "IO_L23N_2/VREF_2_K21") (pintype "bidirectional"))
    )
    (net (code "249") (name "/EXTEND_C9") (class "Default")
      (node (ref "U1") (pin "J21") (pinfunction "IO_L16P_2_J21") (pintype "bidirectional"))
    )
    (net (code "250") (name "/EXTEND_C10") (class "Default")
      (node (ref "U1") (pin "H21") (pinfunction "IO_L14P_2_H21") (pintype "bidirectional"))
    )
    (net (code "251") (name "/EXTEND_C11") (class "Default")
      (node (ref "U1") (pin "G21") (pinfunction "IO_L06P_2_G21") (pintype "bidirectional"))
    )
    (net (code "252") (name "/EXTEND_C12") (class "Default")
      (node (ref "U1") (pin "E26") (pinfunction "IO_L05P_2_E26") (pintype "bidirectional"))
    )
    (net (code "253") (name "/EXTEND_C13") (class "Default")
      (node (ref "U1") (pin "E25") (pinfunction "IO_L05N_2_E25") (pintype "bidirectional"))
    )
    (net (code "254") (name "/EXTEND_C14") (class "Default")
      (node (ref "U1") (pin "C23") (pinfunction "IO_L04P_1_C23") (pintype "bidirectional"))
    )
    (net (code "255") (name "/EXTEND_C15") (class "Default")
      (node (ref "U1") (pin "B22") (pinfunction "IO_L06N_1/VREF_1_B22") (pintype "bidirectional"))
    )
    (net (code "256") (name "/EXTEND_C16") (class "Default")
      (node (ref "U1") (pin "C22") (pinfunction "IO_L06P_1_C22") (pintype "bidirectional"))
    )
    (net (code "257") (name "/EXTEND_C17") (class "Default")
      (node (ref "U1") (pin "D21") (pinfunction "IO_L07P_1_D21") (pintype "bidirectional"))
    )
    (net (code "258") (name "/EXTEND_C18") (class "Default")
      (node (ref "U1") (pin "C21") (pinfunction "IO_L07N_1_C21") (pintype "bidirectional"))
    )
    (net (code "259") (name "/EXTEND_C19") (class "Default")
      (node (ref "U1") (pin "D20") (pinfunction "IO_L09N_1_D20") (pintype "bidirectional"))
    )
    (net (code "260") (name "/EXTEND_C20") (class "Default")
      (node (ref "U1") (pin "D19") (pinfunction "IO_L12P_1_D19") (pintype "bidirectional"))
    )
    (net (code "261") (name "/EXTEND_C21") (class "Default")
      (node (ref "U1") (pin "C19") (pinfunction "IO_L12N_1_C19") (pintype "bidirectional"))
    )
    (net (code "262") (name "/EXTEND_C22") (class "Default")
      (node (ref "U1") (pin "D18") (pinfunction "IO/VREF_1_D18") (pintype "bidirectional"))
    )
    (net (code "263") (name "/EXTEND_C23") (class "Default")
      (node (ref "U1") (pin "C18") (pinfunction "IO_L18P_1_C18") (pintype "bidirectional"))
    )
    (net (code "264") (name "/EXTEND_C24") (class "Default")
      (node (ref "U1") (pin "C17") (pinfunction "IO/VREF_1_C17") (pintype "bidirectional"))
    )
    (net (code "265") (name "/EXTEND_C25") (class "Default")
      (node (ref "U1") (pin "D17") (pinfunction "IO_L22N_1_D17") (pintype "bidirectional"))
    )
    (net (code "266") (name "/EXTEND_C26") (class "Default")
      (node (ref "U1") (pin "D16") (pinfunction "IO_D16") (pintype "bidirectional"))
    )
    (net (code "267") (name "/EXTEND_C27") (class "Default")
      (node (ref "U1") (pin "C15") (pinfunction "IO/VREF_1_C15") (pintype "bidirectional"))
    )
    (net (code "268") (name "/EXTEND_C28") (class "Default")
      (node (ref "U1") (pin "H16") (pinfunction "IO_L24P_1_H16") (pintype "bidirectional"))
    )
    (net (code "269") (name "/EXTEND_C29") (class "Default")
      (node (ref "U1") (pin "D13") (pinfunction "IO_L31N_0_D13") (pintype "bidirectional"))
    )
    (net (code "270") (name "/EXTEND_C30") (class "Default")
      (node (ref "U1") (pin "C13") (pinfunction "IO_L31P_0/VREF_0_C13") (pintype "bidirectional"))
    )
    (net (code "271") (name "/EXTEND_C31") (class "Default")
      (node (ref "U1") (pin "H11") (pinfunction "IO_H11") (pintype "bidirectional"))
    )
    (net (code "272") (name "/EXTEND_C32") (class "Default")
      (node (ref "U1") (pin "C12") (pinfunction "IO_C12") (pintype "bidirectional"))
    )
    (net (code "273") (name "/EXTEND_C33") (class "Default")
      (node (ref "U1") (pin "D11") (pinfunction "IO_L25P_0_D11") (pintype "bidirectional"))
    )
    (net (code "274") (name "/EXTEND_C34") (class "Default")
      (node (ref "U1") (pin "D10") (pinfunction "IO_L22N_0_D10") (pintype "bidirectional"))
    )
    (net (code "275") (name "/EXTEND_C35") (class "Default")
      (node (ref "U1") (pin "C10") (pinfunction "IO_L22P_0_C10") (pintype "bidirectional"))
    )
    (net (code "276") (name "/EXTEND_C36") (class "Default")
      (node (ref "U1") (pin "C9") (pinfunction "IO_L18N_0_C9") (pintype "bidirectional"))
    )
    (net (code "277") (name "/EXTEND_C37") (class "Default")
      (node (ref "U1") (pin "D9") (pinfunction "IO_L17P_0_D9") (pintype "bidirectional"))
    )
    (net (code "278") (name "/EXTEND_C38") (class "Default")
      (node (ref "U1") (pin "C8") (pinfunction "IO_C8") (pintype "bidirectional"))
    )
    (net (code "279") (name "/EXTEND_C39") (class "Default")
      (node (ref "U1") (pin "D8") (pinfunction "IO_L12P_0_D8") (pintype "bidirectional"))
    )
    (net (code "280") (name "/EXTEND_C40") (class "Default")
      (node (ref "U1") (pin "B11") (pinfunction "IO_L26N_0_B11") (pintype "bidirectional"))
    )
    (net (code "281") (name "/EXTEND_C41") (class "Default")
      (node (ref "U1") (pin "D7") (pinfunction "IO_L09P_0_D7") (pintype "bidirectional"))
    )
    (net (code "282") (name "/EXTEND_C42") (class "Default")
      (node (ref "U1") (pin "A10") (pinfunction "IO_L23P_0_A10") (pintype "bidirectional"))
    )
    (net (code "283") (name "/EXTEND_C43") (class "Default")
      (node (ref "U1") (pin "C6") (pinfunction "IO_L08N_0_C6") (pintype "bidirectional"))
    )
    (net (code "284") (name "/EXTEND_C44") (class "Default")
      (node (ref "U1") (pin "B10") (pinfunction "IO_L23N_0_B10") (pintype "bidirectional"))
    )
    (net (code "285") (name "/EXTEND_C45") (class "Default")
      (node (ref "U1") (pin "D6") (pinfunction "IO_L07P_0_D6") (pintype "bidirectional"))
    )
    (net (code "286") (name "/EXTEND_C46") (class "Default")
      (node (ref "U1") (pin "B9") (pinfunction "IO_L18P_0_B9") (pintype "bidirectional"))
    )
    (net (code "287") (name "/EXTEND_C47") (class "Default")
      (node (ref "U1") (pin "C5") (pinfunction "IO_L06N_0_C5") (pintype "bidirectional"))
    )
    (net (code "288") (name "/EXTEND_C48") (class "Default")
      (node (ref "U1") (pin "A8") (pinfunction "IO_L15P_0_A8") (pintype "bidirectional"))
    )
    (net (code "289") (name "/EXTEND_C49") (class "Default")
      (node (ref "U1") (pin "B8") (pinfunction "IO_L15N_0_B8") (pintype "bidirectional"))
    )
    (net (code "291") (name "/FPGA_CCLK") (class "Default")
      (node (ref "R20") (pin "1") (pinfunction "1_1") (pintype "passive"))
    )
    (net (code "292") (name "/FPGA_CLK") (class "Default")
      (node (ref "U1") (pin "AE14") (pinfunction "IO_L32N_4/GCLK1_AE14") (pintype "bidirectional"))
    )
    (net (code "293") (name "/FPGA_CLK1") (class "Default")
      (node (ref "U1") (pin "C14") (pinfunction "IO_L32P_1/GCLK4_C14") (pintype "bidirectional"))
    )
    (net (code "294") (name "/FPGA_DIN") (class "Default")
      (node (ref "U1") (pin "Y15") (pinfunction "IO_L27N_4/DIN/D0_Y15") (pintype "bidirectional"))
    )
    (net (code "295") (name "/FPGA_DONE") (class "Default")
      (node (ref "NT6") (pin "2") (pinfunction "Net2_2") (pintype "passive"))
      (node (ref "R22") (pin "1") (pinfunction "1_1") (pintype "passive"))
      (node (ref "R4") (pin "1") (pinfunction "1_1") (pintype "passive"))
    )
    (net (code "296") (name "/FPGA_ID0") (class "Default")
      (node (ref "NT2") (pin "1") (pinfunction "Net1_1") (pintype "passive"))
    )
    (net (code "297") (name "/FPGA_ID1") (class "Default")
      (node (ref "NT3") (pin "1") (pinfunction "Net1_1") (pintype "passive"))
    )
    (net (code "298") (name "/FPGA_ID2") (class "Default")
      (node (ref "NT4") (pin "1") (pinfunction "Net1_1") (pintype "passive"))
    )
    (net (code "299") (name "/FPGA_ID3") (class "Default")
      (node (ref "NT5") (pin "1") (pinfunction "Net1_1") (pintype "passive"))
    )
    (net (code "301") (name "/FPGA_INIT") (class "Default")
      (node (ref "R3") (pin "1") (pinfunction "1_1") (pintype "passive"))
      (node (ref "U1") (pin "AC14") (pinfunction "IO_L31N_4/INIT_B_AC14") (pintype "bidirectional"))
    )
    (net (code "302") (name "/FPGA_M0") (class "Default")
      (node (ref "R23") (pin "1") (pinfunction "1_1") (pintype "passive"))
    )
    (net (code "303") (name "/FPGA_M1") (class "Default")
      (node (ref "R18") (pin "1") (pinfunction "1_1") (pintype "passive"))
    )
    (net (code "304") (name "/FPGA_M2") (class "Default")
      (node (ref "R14") (pin "1") (pinfunction "1_1") (pintype "passive"))
    )
    (net (code "305") (name "/FPGA_PROGRAM") (class "Default")
      (node (ref "R1") (pin "1") (pinfunction "1_1") (pintype "passive"))
      (node (ref "R24") (pin "1") (pinfunction "1_1") (pintype "passive"))
    )
    (net (code "307") (name "/FPGA_PROG_PWR_ON") (class "Default")
      (node (ref "R7") (pin "1") (pinfunction "1_1") (pintype "passive"))
    )
    (net (code "308") (name "/FPGA_TCK") (class "Default")
      (node (ref "R9") (pin "1") (pinfunction "1_1") (pintype "passive"))
    )
    (net (code "309") (name "/FPGA_TDI") (class "Default")
      (node (ref "R12") (pin "1") (pinfunction "1_1") (pintype "passive"))
    )
    (net (code "310") (name "/FPGA_TDO") (class "Default")
      (node (ref "R10") (pin "1") (pinfunction "1_1") (pintype "passive"))
      (node (ref "R2") (pin "1") (pinfunction "1_1") (pintype "passive"))
    )
    (net (code "311") (name "/FPGA_TMS") (class "Default")
      (node (ref "R8") (pin "1") (pinfunction "1_1") (pintype "passive"))
    )
    (net (code "312") (name "/HSWAP_EN") (class "Default")
      (node (ref "R7") (pin "2") (pinfunction "2_2") (pintype "passive"))
    )
    (net (code "313") (name "/IO0") (class "Default")
      (node (ref "U1") (pin "AE4") (pinfunction "IO_L04N_5_AE4") (pintype "bidirectional"))
    )
    (net (code "314") (name "/IO1") (class "Default")
      (node (ref "U1") (pin "AF4") (pinfunction "IO_AF4") (pintype "bidirectional"))
    )
    (net (code "315") (name "/IO2") (class "Default")
      (node (ref "U1") (pin "AE5") (pinfunction "IO_L06N_5_AE5") (pintype "bidirectional"))
    )
    (net (code "316") (name "/IO3") (class "Default")
      (node (ref "U1") (pin "AF5") (pinfunction "IO/VREF_5_AF5") (pintype "bidirectional"))
    )
    (net (code "317") (name "/IO4") (class "Default")
      (node (ref "U1") (pin "AE6") (pinfunction "IO_L08P_5_AE6") (pintype "bidirectional"))
    )
    (net (code "318") (name "/IO5") (class "Default")
      (node (ref "U1") (pin "AF6") (pinfunction "IO_L08N_5_AF6") (pintype "bidirectional"))
    )
    (net (code "319") (name "/IO6") (class "Default")
      (node (ref "U1") (pin "AB3") (pinfunction "IO_L02P_6_AB3") (pintype "bidirectional"))
    )
    (net (code "320") (name "/IO7") (class "Default")
      (node (ref "U1") (pin "AB4") (pinfunction "IO_L02N_6_AB4") (pintype "bidirectional"))
    )
    (net (code "321") (name "/IO8") (class "Default")
      (node (ref "U1") (pin "AE8") (pinfunction "IO_L15P_5_AE8") (pintype "bidirectional"))
    )
    (net (code "322") (name "/IO9") (class "Default")
      (node (ref "U1") (pin "AF8") (pinfunction "IO_L15N_5_AF8") (pintype "bidirectional"))
    )
    (net (code "323") (name "/IO10") (class "Default")
      (node (ref "U1") (pin "AE9") (pinfunction "IO_L18N_5_AE9") (pintype "bidirectional"))
    )
    (net (code "324") (name "/IO11") (class "Default")
      (node (ref "U1") (pin "AE10") (pinfunction "IO_L23P_5_AE10") (pintype "bidirectional"))
    )
    (net (code "325") (name "/IO12") (class "Default")
      (node (ref "U1") (pin "AF10") (pinfunction "IO_L23N_5_AF10") (pintype "bidirectional"))
    )
    (net (code "326") (name "/IO13") (class "Default")
      (node (ref "U1") (pin "AE11") (pinfunction "IO_L26P_5_AE11") (pintype "bidirectional"))
    )
    (net (code "327") (name "/IO14") (class "Default")
      (node (ref "U1") (pin "AF11") (pinfunction "IO_L26N_5_AF11") (pintype "bidirectional"))
    )
    (net (code "328") (name "/IO15") (class "Default")
      (node (ref "U1") (pin "AE12") (pinfunction "IO_L29P_5/VREF_5_AE12") (pintype "bidirectional"))
    )
    (net (code "329") (name "/IO16") (class "Default")
      (node (ref "U1") (pin "AF12") (pinfunction "IO_L29N_5_AF12") (pintype "bidirectional"))
    )
    (net (code "330") (name "/IO17") (class "Default")
      (node (ref "U1") (pin "AF13") (pinfunction "IO/VREF_5_AF13") (pintype "bidirectional"))
    )
    (net (code "331") (name "/IO18") (class "Default")
      (node (ref "U1") (pin "AE15") (pinfunction "IO_L29N_4_AE15") (pintype "bidirectional"))
    )
    (net (code "332") (name "/IO19") (class "Default")
      (node (ref "U1") (pin "AF16") (pinfunction "IO_L26P_4/VREF_4_AF16") (pintype "bidirectional"))
    )
    (net (code "333") (name "/IO20") (class "Default")
      (node (ref "U1") (pin "AE16") (pinfunction "IO_L26N_4_AE16") (pintype "bidirectional"))
    )
    (net (code "334") (name "/IO21") (class "Default")
      (node (ref "U1") (pin "AF17") (pinfunction "IO_L23P_4_AF17") (pintype "bidirectional"))
    )
    (net (code "335") (name "/IO22") (class "Default")
      (node (ref "U1") (pin "AE17") (pinfunction "IO_L23N_4_AE17") (pintype "bidirectional"))
    )
    (net (code "336") (name "/IO23") (class "Default")
      (node (ref "U1") (pin "AE18") (pinfunction "IO_L18P_4_AE18") (pintype "bidirectional"))
    )
    (net (code "337") (name "/IO24") (class "Default")
      (node (ref "U1") (pin "AF19") (pinfunction "IO_L15P_4_AF19") (pintype "bidirectional"))
    )
    (net (code "338") (name "/IO25") (class "Default")
      (node (ref "U1") (pin "AE19") (pinfunction "IO_L15N_4_AE19") (pintype "bidirectional"))
    )
    (net (code "339") (name "/IO26") (class "Default")
      (node (ref "U1") (pin "AF20") (pinfunction "IO_L10P_4_AF20") (pintype "bidirectional"))
    )
    (net (code "340") (name "/IO27") (class "Default")
      (node (ref "U1") (pin "AE20") (pinfunction "IO_L10N_4_AE20") (pintype "bidirectional"))
    )
    (net (code "341") (name "/IO28") (class "Default")
      (node (ref "U1") (pin "AF21") (pinfunction "IO_AF21") (pintype "bidirectional"))
    )
    (net (code "342") (name "/IO29") (class "Default")
      (node (ref "U1") (pin "AE21") (pinfunction "IO_L08P_4_AE21") (pintype "bidirectional"))
    )
    (net (code "343") (name "/IO30") (class "Default")
      (node (ref "U1") (pin "AF22") (pinfunction "IO_AF22") (pintype "bidirectional"))
    )
    (net (code "344") (name "/IO31") (class "Default")
      (node (ref "U1") (pin "AE22") (pinfunction "IO_L06P_4_AE22") (pintype "bidirectional"))
    )
    (net (code "345") (name "/IO32") (class "Default")
      (node (ref "U1") (pin "AF23") (pinfunction "IO_L05P_4_AF23") (pintype "bidirectional"))
    )
    (net (code "346") (name "/IO33") (class "Default")
      (node (ref "U1") (pin "AE23") (pinfunction "IO_L05N_4_AE23") (pintype "bidirectional"))
    )
    (net (code "347") (name "/IO34") (class "Default")
      (node (ref "U1") (pin "AF24") (pinfunction "IO_L04P_4_AF24") (pintype "bidirectional"))
    )
    (net (code "348") (name "/IO35") (class "Default")
      (node (ref "U1") (pin "AE24") (pinfunction "IO_L04N_4_AE24") (pintype "bidirectional"))
    )
    (net (code "349") (name "/KBCLOCK") (class "Default")
      (node (ref "U1") (pin "A16") (pinfunction "IO_L26N_1_A16") (pintype "bidirectional"))
    )
    (net (code "350") (name "/KBDATA") (class "Default")
      (node (ref "U1") (pin "B16") (pinfunction "IO_L26P_1_B16") (pintype "bidirectional"))
    )
    (net (code "351") (name "/LED0") (class "Default")
      (node (ref "U1") (pin "AD6") (pinfunction "IO_L07N_5_AD6") (pintype "bidirectional"))
    )
    (net (code "352") (name "/LED1") (class "Default")
      (node (ref "U1") (pin "AC7") (pinfunction "IO_L09N_5_AC7") (pintype "bidirectional"))
    )
    (net (code "353") (name "/LED2") (class "Default")
      (node (ref "U1") (pin "AC8") (pinfunction "IO_L12P_5_AC8") (pintype "bidirectional"))
    )
    (net (code "354") (name "/LED3") (class "Default")
      (node (ref "U1") (pin "AD8") (pinfunction "IO_L12N_5_AD8") (pintype "bidirectional"))
    )
    (net (code "355") (name "/LED4") (class "Default")
      (node (ref "U1") (pin "AC9") (pinfunction "IO_AC9") (pintype "bidirectional"))
    )
    (net (code "356") (name "/LED5") (class "Default")
      (node (ref "U1") (pin "AD9") (pinfunction "IO_L18P_5_AD9") (pintype "bidirectional"))
    )
    (net (code "357") (name "/LED6") (class "Default")
      (node (ref "U1") (pin "AD10") (pinfunction "IO_AD10") (pintype "bidirectional"))
    )
    (net (code "358") (name "/LED7") (class "Default")
      (node (ref "U1") (pin "AC10") (pinfunction "IO_L22N_5_AC10") (pintype "bidirectional"))
    )
    (net (code "359") (name "/M0") (class "Default")
      (node (ref "R23") (pin "2") (pinfunction "2_2") (pintype "passive"))
    )
    (net (code "360") (name "/M1") (class "Default")
      (node (ref "R18") (pin "2") (pinfunction "2_2") (pintype "passive"))
    )
    (net (code "361") (name "/M2") (class "Default")
      (node (ref "R14") (pin "2") (pinfunction "2_2") (pintype "passive"))
    )
    (net (code "362") (name "/MOUSECLOCK") (class "Default")
      (node (ref "U1") (pin "A17") (pinfunction "IO_L23N_1_A17") (pintype "bidirectional"))
    )
    (net (code "363") (name "/MOUSEDATA") (class "Default")
      (node (ref "U1") (pin "B17") (pinfunction "IO_L23P_1_B17") (pintype "bidirectional"))
    )
    (net (code "364") (name "/NEXUS_TCK") (class "Default")
      (node (ref "U1") (pin "P21") (pinfunction "IO_L38P_3_P21") (pintype "bidirectional"))
    )
    (net (code "365") (name "/NEXUS_TDI") (class "Default")
      (node (ref "U1") (pin "R21") (pinfunction "IO_L32P_3_R21") (pintype "bidirectional"))
    )
    (net (code "366") (name "/NEXUS_TDO") (class "Default")
      (node (ref "U1") (pin "B23") (pinfunction "IO_L04N_1_B23") (pintype "bidirectional"))
    )
    (net (code "367") (name "/NEXUS_TMS") (class "Default")
      (node (ref "U1") (pin "P19") (pinfunction "IO_L35P_3_P19") (pintype "bidirectional"))
    )
    (net (code "369") (name "/ONE_WIRE_DB_PB") (class "Default")
      (node (ref "U1") (pin "AA8") (pinfunction "IO_L11P_5_AA8") (pintype "bidirectional"))
    )
    (net (code "373") (name "/PROG_B") (class "Default")
      (node (ref "R24") (pin "2") (pinfunction "2_2") (pintype "passive"))
    )
    (net (code "374") (name "/REF_CLK") (class "Default")
      (node (ref "U1") (pin "AF14") (pinfunction "IO_L32P_4/GCLK0_AF14") (pintype "bidirectional"))
    )
    (net (code "375") (name "/RS232_CTS") (class "Default")
      (node (ref "U1") (pin "A15") (pinfunction "IO_L29N_1_A15") (pintype "bidirectional"))
    )
    (net (code "376") (name "/RS232_RTS") (class "Default")
      (node (ref "U1") (pin "A12") (pinfunction "IO_L29P_0_A12") (pintype "bidirectional"))
    )
    (net (code "377") (name "/RS232_RX") (class "Default")
      (node (ref "U1") (pin "B15") (pinfunction "IO_L29P_1_B15") (pintype "bidirectional"))
    )
    (net (code "378") (name "/RS232_TX") (class "Default")
      (node (ref "U1") (pin "A14") (pinfunction "IO_A14") (pintype "bidirectional"))
    )
    (net (code "379") (name "/SCL") (class "Default")
      (node (ref "U1") (pin "AA7") (pinfunction "IO_AA7") (pintype "bidirectional"))
    )
    (net (code "380") (name "/SDA") (class "Default")
      (node (ref "U1") (pin "AA6") (pinfunction "IO_L05P_5_AA6") (pintype "bidirectional"))
    )
    (net (code "381") (name "/SPI_CLK") (class "Default")
      (node (ref "U1") (pin "E13") (pinfunction "IO_E13") (pintype "bidirectional"))
    )
    (net (code "382") (name "/SPI_DIN") (class "Default")
      (node (ref "U1") (pin "H12") (pinfunction "IO_H12") (pintype "bidirectional"))
    )
    (net (code "383") (name "/SPI_DOUT") (class "Default")
      (node (ref "U1") (pin "H15") (pinfunction "IO_L27P_1_H15") (pintype "bidirectional"))
    )
    (net (code "384") (name "/SPI_MODE") (class "Default")
      (node (ref "U1") (pin "E15") (pinfunction "IO_L28N_1_E15") (pintype "bidirectional"))
    )
    (net (code "385") (name "/SPI_SEL") (class "Default")
      (node (ref "U1") (pin "E14") (pinfunction "IO_L31P_1_E14") (pintype "bidirectional"))
    )
    (net (code "386") (name "/SRAM1_A0") (class "Default")
      (node (ref "U1") (pin "AC18") (pinfunction "IO_L17P_4_AC18") (pintype "bidirectional"))
    )
    (net (code "387") (name "/SRAM1_A1") (class "Default")
      (node (ref "U1") (pin "AC19") (pinfunction "IO_L12P_4_AC19") (pintype "bidirectional"))
    )
    (net (code "388") (name "/SRAM1_A2") (class "Default")
      (node (ref "U1") (pin "AD21") (pinfunction "IO_L08N_4_AD21") (pintype "bidirectional"))
    )
    (net (code "389") (name "/SRAM1_A3") (class "Default")
      (node (ref "U1") (pin "AD22") (pinfunction "IO_L06N_4/VREF_4_AD22") (pintype "bidirectional"))
    )
    (net (code "390") (name "/SRAM1_A4") (class "Default")
      (node (ref "U1") (pin "AD23") (pinfunction "IO_AD23") (pintype "bidirectional"))
    )
    (net (code "391") (name "/SRAM1_A5") (class "Default")
      (node (ref "U1") (pin "Y16") (pinfunction "IO_L24N_4_Y16") (pintype "bidirectional"))
    )
    (net (code "392") (name "/SRAM1_A6") (class "Default")
      (node (ref "U1") (pin "Y17") (pinfunction "IO/VREF_4_Y17") (pintype "bidirectional"))
    )
    (net (code "393") (name "/SRAM1_A7") (class "Default")
      (node (ref "U1") (pin "Y18") (pinfunction "IO_L16N_4_Y18") (pintype "bidirectional"))
    )
    (net (code "394") (name "/SRAM1_A8") (class "Default")
      (node (ref "U1") (pin "Y19") (pinfunction "IO_L11N_4_Y19") (pintype "bidirectional"))
    )
    (net (code "395") (name "/SRAM1_A9") (class "Default")
      (node (ref "U1") (pin "Y20") (pinfunction "IO_L05P_3_Y20") (pintype "bidirectional"))
    )
    (net (code "396") (name "/SRAM1_A10") (class "Default")
      (node (ref "U1") (pin "Y21") (pinfunction "IO_L05N_3_Y21") (pintype "bidirectional"))
    )
    (net (code "397") (name "/SRAM1_A11") (class "Default")
      (node (ref "U1") (pin "AA20") (pinfunction "IO_AA20") (pintype "bidirectional"))
    )
    (net (code "398") (name "/SRAM1_A12") (class "Default")
      (node (ref "U1") (pin "AA19") (pinfunction "IO_L11P_4_AA19") (pintype "bidirectional"))
    )
    (net (code "399") (name "/SRAM1_A13") (class "Default")
      (node (ref "U1") (pin "AA18") (pinfunction "IO_L16P_4_AA18") (pintype "bidirectional"))
    )
    (net (code "400") (name "/SRAM1_A14") (class "Default")
      (node (ref "U1") (pin "AA17") (pinfunction "IO_L19P_4_AA17") (pintype "bidirectional"))
    )
    (net (code "401") (name "/SRAM1_A15") (class "Default")
      (node (ref "U1") (pin "AD18") (pinfunction "IO_L18N_4_AD18") (pintype "bidirectional"))
    )
    (net (code "402") (name "/SRAM1_A16") (class "Default")
      (node (ref "U1") (pin "AD17") (pinfunction "IO_L22N_4/VREF_4_AD17") (pintype "bidirectional"))
    )
    (net (code "403") (name "/SRAM1_A17") (class "Default")
      (node (ref "U1") (pin "AC17") (pinfunction "IO_L19N_4_AC17") (pintype "bidirectional"))
    )
    (net (code "404") (name "/SRAM1_A18") (class "Default")
      (node (ref "U1") (pin "AA16") (pinfunction "IO_L24P_4_AA16") (pintype "bidirectional"))
    )
    (net (code "406") (name "/SRAM1_D0") (class "Default")
      (node (ref "U1") (pin "W15") (pinfunction "IO_W15") (pintype "bidirectional"))
    )
    (net (code "407") (name "/SRAM1_D1") (class "Default")
      (node (ref "U1") (pin "AB15") (pinfunction "IO_L28P_4_AB15") (pintype "bidirectional"))
    )
    (net (code "408") (name "/SRAM1_D2") (class "Default")
      (node (ref "U1") (pin "AB16") (pinfunction "IO_L25N_4_AB16") (pintype "bidirectional"))
    )
    (net (code "409") (name "/SRAM1_D3") (class "Default")
      (node (ref "U1") (pin "AB17") (pinfunction "IO_L22P_4_AB17") (pintype "bidirectional"))
    )
    (net (code "410") (name "/SRAM1_D4") (class "Default")
      (node (ref "U1") (pin "AB18") (pinfunction "IO_L17N_4_AB18") (pintype "bidirectional"))
    )
    (net (code "411") (name "/SRAM1_D5") (class "Default")
      (node (ref "U1") (pin "AB19") (pinfunction "IO_L12N_4_AB19") (pintype "bidirectional"))
    )
    (net (code "412") (name "/SRAM1_D6") (class "Default")
      (node (ref "U1") (pin "AB20") (pinfunction "IO_L09N_4_AB20") (pintype "bidirectional"))
    )
    (net (code "413") (name "/SRAM1_D7") (class "Default")
      (node (ref "U1") (pin "AB21") (pinfunction "IO_L07N_4_AB21") (pintype "bidirectional"))
    )
    (net (code "414") (name "/SRAM1_D8") (class "Default")
      (node (ref "U1") (pin "AA15") (pinfunction "IO_L28N_4_AA15") (pintype "bidirectional"))
    )
    (net (code "415") (name "/SRAM1_D9") (class "Default")
      (node (ref "U1") (pin "AA14") (pinfunction "IO_L30P_4/D3_AA14") (pintype "bidirectional"))
    )
    (net (code "416") (name "/SRAM1_D10") (class "Default")
      (node (ref "U1") (pin "W14") (pinfunction "IO_L27P_4/D1_W14") (pintype "bidirectional"))
    )
    (net (code "417") (name "/SRAM1_D11") (class "Default")
      (node (ref "U1") (pin "AD25") (pinfunction "IO/VREF_4_AD25") (pintype "bidirectional"))
    )
    (net (code "418") (name "/SRAM1_D12") (class "Default")
      (node (ref "U1") (pin "AC21") (pinfunction "IO_L07P_4_AC21") (pintype "bidirectional"))
    )
    (net (code "419") (name "/SRAM1_D13") (class "Default")
      (node (ref "U1") (pin "AC20") (pinfunction "IO_L09P_4_AC20") (pintype "bidirectional"))
    )
    (net (code "420") (name "/SRAM1_D14") (class "Default")
      (node (ref "U1") (pin "AD19") (pinfunction "IO_AD19") (pintype "bidirectional"))
    )
    (net (code "421") (name "/SRAM1_D15") (class "Default")
      (node (ref "U1") (pin "AD14") (pinfunction "IO_L31P_4/DOUT/BUSY_AD14") (pintype "bidirectional"))
    )
    (net (code "423") (name "/SRAM1_NBHE") (class "Default")
      (node (ref "U1") (pin "AD15") (pinfunction "IO_AD15") (pintype "bidirectional"))
    )
    (net (code "424") (name "/SRAM1_NBLE") (class "Default")
      (node (ref "U1") (pin "W16") (pinfunction "IO_W16") (pintype "bidirectional"))
    )
    (net (code "425") (name "/SRAM1_NCS") (class "Default")
      (node (ref "U1") (pin "AB14") (pinfunction "IO/VREF_4_AB14") (pintype "bidirectional"))
    )
    (net (code "426") (name "/SRAM1_NOE") (class "Default")
      (node (ref "U1") (pin "AC16") (pinfunction "IO_L25P_4_AC16") (pintype "bidirectional"))
    )
    (net (code "427") (name "/SRAM1_NWE") (class "Default")
      (node (ref "U1") (pin "Y14") (pinfunction "IO_L30N_4/D2_Y14") (pintype "bidirectional"))
    )
    (net (code "428") (name "/SRAM2_A0") (class "Default")
      (node (ref "U1") (pin "T22") (pinfunction "IO_L28N_3_T22") (pintype "bidirectional"))
    )
    (net (code "429") (name "/SRAM2_A1") (class "Default")
      (node (ref "U1") (pin "R22") (pinfunction "IO_L32N_3_R22") (pintype "bidirectional"))
    )
    (net (code "430") (name "/SRAM2_A2") (class "Default")
      (node (ref "U1") (pin "R19") (pinfunction "IO_L31P_3_R19") (pintype "bidirectional"))
    )
    (net (code "431") (name "/SRAM2_A3") (class "Default")
      (node (ref "U1") (pin "P22") (pinfunction "IO_L38N_3_P22") (pintype "bidirectional"))
    )
    (net (code "432") (name "/SRAM2_A4") (class "Default")
      (node (ref "U1") (pin "AB23") (pinfunction "IO_L02P_3_AB23") (pintype "bidirectional"))
    )
    (net (code "433") (name "/SRAM2_A5") (class "Default")
      (node (ref "U1") (pin "T23") (pinfunction "IO_L33P_3_T23") (pintype "bidirectional"))
    )
    (net (code "434") (name "/SRAM2_A6") (class "Default")
      (node (ref "U1") (pin "R24") (pinfunction "IO_L33N_3_R24") (pintype "bidirectional"))
    )
    (net (code "435") (name "/SRAM2_A7") (class "Default")
      (node (ref "U1") (pin "T19") (pinfunction "IO_L27P_3_T19") (pintype "bidirectional"))
    )
    (net (code "436") (name "/SRAM2_A8") (class "Default")
      (node (ref "U1") (pin "P24") (pinfunction "IO_L39N_3_P24") (pintype "bidirectional"))
    )
    (net (code "437") (name "/SRAM2_A9") (class "Default")
      (node (ref "U1") (pin "P23") (pinfunction "IO_L39P_3_P23") (pintype "bidirectional"))
    )
    (net (code "438") (name "/SRAM2_A10") (class "Default")
      (node (ref "U1") (pin "P26") (pinfunction "IO_L40N_3/VREF_3_P26") (pintype "bidirectional"))
    )
    (net (code "439") (name "/SRAM2_A11") (class "Default")
      (node (ref "U1") (pin "P25") (pinfunction "IO_L40P_3_P25") (pintype "bidirectional"))
    )
    (net (code "440") (name "/SRAM2_A12") (class "Default")
      (node (ref "U1") (pin "R26") (pinfunction "IO_L34N_3_R26") (pintype "bidirectional"))
    )
    (net (code "441") (name "/SRAM2_A13") (class "Default")
      (node (ref "U1") (pin "R25") (pinfunction "IO_L34P_3/VREF_3_R25") (pintype "bidirectional"))
    )
    (net (code "442") (name "/SRAM2_A14") (class "Default")
      (node (ref "U1") (pin "T26") (pinfunction "IO_L29N_3_T26") (pintype "bidirectional"))
    )
    (net (code "443") (name "/SRAM2_A15") (class "Default")
      (node (ref "U1") (pin "AC26") (pinfunction "IO_L03N_3_AC26") (pintype "bidirectional"))
    )
    (net (code "444") (name "/SRAM2_A16") (class "Default")
      (node (ref "U1") (pin "AC25") (pinfunction "IO_L03P_3_AC25") (pintype "bidirectional"))
    )
    (net (code "445") (name "/SRAM2_A17") (class "Default")
      (node (ref "U1") (pin "Y22") (pinfunction "IO_L08P_3_Y22") (pintype "bidirectional"))
    )
    (net (code "446") (name "/SRAM2_A18") (class "Default")
      (node (ref "U1") (pin "T25") (pinfunction "IO_L29P_3_T25") (pintype "bidirectional"))
    )
    (net (code "448") (name "/SRAM2_D0") (class "Default")
      (node (ref "U1") (pin "AA23") (pinfunction "IO_L07P_3_AA23") (pintype "bidirectional"))
    )
    (net (code "449") (name "/SRAM2_D1") (class "Default")
      (node (ref "U1") (pin "AA24") (pinfunction "IO_L07N_3_AA24") (pintype "bidirectional"))
    )
    (net (code "450") (name "/SRAM2_D2") (class "Default")
      (node (ref "U1") (pin "Y23") (pinfunction "IO_L08N_3_Y23") (pintype "bidirectional"))
    )
    (net (code "451") (name "/SRAM2_D3") (class "Default")
      (node (ref "U1") (pin "W23") (pinfunction "IO_L17P_3/VREF_3_W23") (pintype "bidirectional"))
    )
    (net (code "452") (name "/SRAM2_D4") (class "Default")
      (node (ref "U1") (pin "W24") (pinfunction "IO_L17N_3_W24") (pintype "bidirectional"))
    )
    (net (code "453") (name "/SRAM2_D5") (class "Default")
      (node (ref "U1") (pin "V23") (pinfunction "IO_L21N_3_V23") (pintype "bidirectional"))
    )
    (net (code "454") (name "/SRAM2_D6") (class "Default")
      (node (ref "U1") (pin "V24") (pinfunction "IO_L22P_3_V24") (pintype "bidirectional"))
    )
    (net (code "455") (name "/SRAM2_D7") (class "Default")
      (node (ref "U1") (pin "U24") (pinfunction "IO_L24N_3_U24") (pintype "bidirectional"))
    )
    (net (code "456") (name "/SRAM2_D8") (class "Default")
      (node (ref "U1") (pin "U26") (pinfunction "IO_L26N_3_U26") (pintype "bidirectional"))
    )
    (net (code "457") (name "/SRAM2_D9") (class "Default")
      (node (ref "U1") (pin "U25") (pinfunction "IO_L26P_3_U25") (pintype "bidirectional"))
    )
    (net (code "458") (name "/SRAM2_D10") (class "Default")
      (node (ref "U1") (pin "V25") (pinfunction "IO_L22N_3_V25") (pintype "bidirectional"))
    )
    (net (code "459") (name "/SRAM2_D11") (class "Default")
      (node (ref "U1") (pin "W26") (pinfunction "IO_L19N_3_W26") (pintype "bidirectional"))
    )
    (net (code "460") (name "/SRAM2_D12") (class "Default")
      (node (ref "U1") (pin "W25") (pinfunction "IO_L19P_3_W25") (pintype "bidirectional"))
    )
    (net (code "461") (name "/SRAM2_D13") (class "Default")
      (node (ref "U1") (pin "Y26") (pinfunction "IO_L14N_3_Y26") (pintype "bidirectional"))
    )
    (net (code "462") (name "/SRAM2_D14") (class "Default")
      (node (ref "U1") (pin "Y25") (pinfunction "IO_L14P_3_Y25") (pintype "bidirectional"))
    )
    (net (code "463") (name "/SRAM2_D15") (class "Default")
      (node (ref "U1") (pin "AA26") (pinfunction "IO_L09N_3_AA26") (pintype "bidirectional"))
    )
    (net (code "464") (name "/SRAM2_NBHE") (class "Default")
      (node (ref "U1") (pin "AB26") (pinfunction "IO_L06N_3_AB26") (pintype "bidirectional"))
    )
    (net (code "465") (name "/SRAM2_NBLE") (class "Default")
      (node (ref "U1") (pin "AA25") (pinfunction "IO_L09P_3/VREF_3_AA25") (pintype "bidirectional"))
    )
    (net (code "466") (name "/SRAM2_NCS") (class "Default")
      (node (ref "U1") (pin "AB24") (pinfunction "IO_L02N_3/VREF_3_AB24") (pintype "bidirectional"))
    )
    (net (code "467") (name "/SRAM2_NOE") (class "Default")
      (node (ref "U1") (pin "AB25") (pinfunction "IO_L06P_3_AB25") (pintype "bidirectional"))
    )
    (net (code "468") (name "/SRAM2_NWE") (class "Default")
      (node (ref "U1") (pin "U23") (pinfunction "IO_L24P_3_U23") (pintype "bidirectional"))
    )
    (net (code "470") (name "/STATUS_LED") (class "Default")
      (node (ref "NT6") (pin "1") (pinfunction "Net1_1") (pintype "passive"))
    )
    (net (code "471") (name "/SW0") (class "Default")
      (node (ref "U1") (pin "AB8") (pinfunction "IO_L11N_5/VREF_5_AB8") (pintype "bidirectional"))
    )
    (net (code "472") (name "/SW1") (class "Default")
      (node (ref "U1") (pin "AB9") (pinfunction "IO_AB9") (pintype "bidirectional"))
    )
    (net (code "473") (name "/SW2") (class "Default")
      (node (ref "U1") (pin "AB10") (pinfunction "IO_L22P_5_AB10") (pintype "bidirectional"))
    )
    (net (code "474") (name "/SW3") (class "Default")
      (node (ref "U1") (pin "AB11") (pinfunction "IO_L25N_5_AB11") (pintype "bidirectional"))
    )
    (net (code "475") (name "/SW4") (class "Default")
      (node (ref "U1") (pin "AB12") (pinfunction "IO_L28N_5/D6_AB12") (pintype "bidirectional"))
    )
    (net (code "477") (name "/TCK") (class "Default")
      (node (ref "R9") (pin "2") (pinfunction "2_2") (pintype "passive"))
    )
    (net (code "478") (name "/TDI") (class "Default")
      (node (ref "R12") (pin "2") (pinfunction "2_2") (pintype "passive"))
    )
    (net (code "479") (name "/TDO") (class "Default")
      (node (ref "R10") (pin "2") (pinfunction "2_2") (pintype "passive"))
    )
    (net (code "481") (name "/TMS") (class "Default")
      (node (ref "R8") (pin "2") (pinfunction "2_2") (pintype "passive"))
    )
    (net (code "482") (name "/UGCLK0") (class "Default")
      (node (ref "U1") (pin "B13") (pinfunction "IO_L32N_0/GCLK7_B13") (pintype "bidirectional"))
    )
    (net (code "483") (name "/UGCLK1") (class "Default")
      (node (ref "U1") (pin "AE13") (pinfunction "IO_L32N_5/GCLK3_AE13") (pintype "bidirectional"))
    )
    (net (code "484") (name "/UGCLK2") (class "Default")
      (node (ref "U1") (pin "AD13") (pinfunction "IO_L32P_5/GCLK2_AD13") (pintype "bidirectional"))
    )
    (net (code "505") (name "3V3") (class "Default")
      (node (ref "R1") (pin "2") (pinfunction "2_2") (pintype "passive"))
      (node (ref "R2") (pin "2") (pinfunction "2_2") (pintype "passive"))
      (node (ref "R3") (pin "2") (pinfunction "2_2") (pintype "passive"))
      (node (ref "R4") (pin "2") (pinfunction "2_2") (pintype "passive"))
    )
    (net (code "506") (name "GND") (class "Default")
      (node (ref "NT2") (pin "2") (pinfunction "Net2_2") (pintype "passive"))
      (node (ref "NT3") (pin "2") (pinfunction "Net2_2") (pintype "passive"))
      (node (ref "NT4") (pin "2") (pinfunction "Net2_2") (pintype "passive"))
      (node (ref "NT5") (pin "2") (pinfunction "Net2_2") (pintype "passive"))
    )
    (net (code "507") (name "unconnected-(U1A-IO-PadA3)") (class "Default")
      (node (ref "U1") (pin "A3") (pinfunction "IO_A3") (pintype "bidirectional"))
    )
    (net (code "508") (name "unconnected-(U1A-IO-PadA5)") (class "Default")
      (node (ref "U1") (pin "A5") (pinfunction "IO_A5") (pintype "bidirectional"))
    )
    (net (code "509") (name "unconnected-(U1A-IO-PadA6)") (class "Default")
      (node (ref "U1") (pin "A6") (pinfunction "IO_A6") (pintype "bidirectional+no_connect"))
    )
    (net (code "510") (name "unconnected-(U1A-IO_L01N_0{slash}VRP_0-PadE5)") (class "Default")
      (node (ref "U1") (pin "E5") (pinfunction "IO_L01N_0/VRP_0_E5") (pintype "bidirectional"))
    )
    (net (code "511") (name "unconnected-(U1A-IO_L01P_0{slash}VRN_0-PadD5)") (class "Default")
      (node (ref "U1") (pin "D5") (pinfunction "IO_L01P_0/VRN_0_D5") (pintype "bidirectional"))
    )
    (net (code "512") (name "unconnected-(U1A-IO_L05P_0{slash}VREF_0-PadA4)") (class "Default")
      (node (ref "U1") (pin "A4") (pinfunction "IO_L05P_0/VREF_0_A4") (pintype "bidirectional"))
    )
    (net (code "513") (name "unconnected-(U1A-IO_L06P_0-PadB5)") (class "Default")
      (node (ref "U1") (pin "B5") (pinfunction "IO_L06P_0_B5") (pintype "bidirectional"))
    )
    (net (code "514") (name "unconnected-(U1A-IO_L08P_0-PadB6)") (class "Default")
      (node (ref "U1") (pin "B6") (pinfunction "IO_L08P_0_B6") (pintype "bidirectional+no_connect"))
    )
    (net (code "515") (name "unconnected-(U1A-IO_L10N_0-PadB7)") (class "Default")
      (node (ref "U1") (pin "B7") (pinfunction "IO_L10N_0_B7") (pintype "bidirectional+no_connect"))
    )
    (net (code "516") (name "unconnected-(U1A-IO_L10P_0-PadA7)") (class "Default")
      (node (ref "U1") (pin "A7") (pinfunction "IO_L10P_0_A7") (pintype "bidirectional"))
    )
    (net (code "517") (name "unconnected-(U1A-IO_L16N_0-PadG9)") (class "Default")
      (node (ref "U1") (pin "G9") (pinfunction "IO_L16N_0_G9") (pintype "bidirectional"))
    )
    (net (code "518") (name "unconnected-(U1A-IO_L17N_0-PadE9)") (class "Default")
      (node (ref "U1") (pin "E9") (pinfunction "IO_L17N_0_E9") (pintype "bidirectional"))
    )
    (net (code "519") (name "unconnected-(U1A-IO_L24N_0-PadG11)") (class "Default")
      (node (ref "U1") (pin "G11") (pinfunction "IO_L24N_0_G11") (pintype "bidirectional"))
    )
    (net (code "520") (name "unconnected-(U1A-IO_L27N_0-PadG12)") (class "Default")
      (node (ref "U1") (pin "G12") (pinfunction "IO_L27N_0_G12") (pintype "bidirectional"))
    )
    (net (code "521") (name "unconnected-(U1A-IO_L30N_0-PadG13)") (class "Default")
      (node (ref "U1") (pin "G13") (pinfunction "IO_L30N_0_G13") (pintype "bidirectional"))
    )
    (net (code "522") (name "unconnected-(U1A-IO{slash}VREF_0-PadB3)") (class "Default")
      (node (ref "U1") (pin "B3") (pinfunction "IO/VREF_0_B3") (pintype "bidirectional"))
    )
    (net (code "523") (name "unconnected-(U1A-IO{slash}VREF_0-PadF7)") (class "Default")
      (node (ref "U1") (pin "F7") (pinfunction "IO/VREF_0_F7") (pintype "bidirectional+no_connect"))
    )
    (net (code "524") (name "unconnected-(U1A-IO{slash}VREF_0-PadG10)") (class "Default")
      (node (ref "U1") (pin "G10") (pinfunction "IO/VREF_0_G10") (pintype "bidirectional"))
    )
    (net (code "525") (name "unconnected-(U1B-IO_L01N_1{slash}VRP_1-PadD22)") (class "Default")
      (node (ref "U1") (pin "D22") (pinfunction "IO_L01N_1/VRP_1_D22") (pintype "bidirectional"))
    )
    (net (code "526") (name "unconnected-(U1B-IO_L01P_1{slash}VRN_1-PadE22)") (class "Default")
      (node (ref "U1") (pin "E22") (pinfunction "IO_L01P_1/VRN_1_E22") (pintype "bidirectional"))
    )
    (net (code "527") (name "unconnected-(U1B-IO_L18N_1-PadB18)") (class "Default")
      (node (ref "U1") (pin "B18") (pinfunction "IO_L18N_1_B18") (pintype "bidirectional+no_connect"))
    )
    (net (code "528") (name "unconnected-(U1B-IO_L24N_1-PadG16)") (class "Default")
      (node (ref "U1") (pin "G16") (pinfunction "IO_L24N_1_G16") (pintype "bidirectional"))
    )
    (net (code "529") (name "unconnected-(U1B-IO_L25N_1-PadE16)") (class "Default")
      (node (ref "U1") (pin "E16") (pinfunction "IO_L25N_1_E16") (pintype "bidirectional"))
    )
    (net (code "530") (name "unconnected-(U1B-IO_L27N_1-PadG15)") (class "Default")
      (node (ref "U1") (pin "G15") (pinfunction "IO_L27N_1_G15") (pintype "bidirectional"))
    )
    (net (code "531") (name "unconnected-(U1B-IO_L30N_1-PadG14)") (class "Default")
      (node (ref "U1") (pin "G14") (pinfunction "IO_L30N_1_G14") (pintype "bidirectional"))
    )
    (net (code "532") (name "unconnected-(U1B-IO_L31N_1{slash}VREF_1-PadD14)") (class "Default")
      (node (ref "U1") (pin "D14") (pinfunction "IO_L31N_1/VREF_1_D14") (pintype "bidirectional"))
    )
    (net (code "533") (name "unconnected-(U1B-IO_L32N_1{slash}GCLK5-PadB14)") (class "Default")
      (node (ref "U1") (pin "B14") (pinfunction "IO_L32N_1/GCLK5_B14") (pintype "bidirectional"))
    )
    (net (code "534") (name "unconnected-(U1C-IO_L01N_2{slash}VRP_2-PadC25)") (class "Default")
      (node (ref "U1") (pin "C25") (pinfunction "IO_L01N_2/VRP_2_C25") (pintype "bidirectional"))
    )
    (net (code "535") (name "unconnected-(U1C-IO_L01P_2{slash}VRN_2-PadC26)") (class "Default")
      (node (ref "U1") (pin "C26") (pinfunction "IO_L01P_2/VRN_2_C26") (pintype "bidirectional"))
    )
    (net (code "536") (name "unconnected-(U1C-IO_L03N_2{slash}VREF_2-PadD25)") (class "Default")
      (node (ref "U1") (pin "D25") (pinfunction "IO_L03N_2/VREF_2_D25") (pintype "bidirectional"))
    )
    (net (code "537") (name "unconnected-(U1C-IO_L03P_2-PadD26)") (class "Default")
      (node (ref "U1") (pin "D26") (pinfunction "IO_L03P_2_D26") (pintype "bidirectional"))
    )
    (net (code "538") (name "unconnected-(U1C-IO_L10N_2-PadG25)") (class "Default")
      (node (ref "U1") (pin "G25") (pinfunction "IO_L10N_2_G25") (pintype "bidirectional"))
    )
    (net (code "539") (name "unconnected-(U1C-IO_L14N_2-PadH20)") (class "Default")
      (node (ref "U1") (pin "H20") (pinfunction "IO_L14N_2_H20") (pintype "bidirectional"))
    )
    (net (code "540") (name "unconnected-(U1C-IO_L24N_2-PadK23)") (class "Default")
      (node (ref "U1") (pin "K23") (pinfunction "IO_L24N_2_K23") (pintype "bidirectional"))
    )
    (net (code "541") (name "unconnected-(U1C-IO_L35P_2-PadN20)") (class "Default")
      (node (ref "U1") (pin "N20") (pinfunction "IO_L35P_2_N20") (pintype "bidirectional"))
    )
    (net (code "542") (name "unconnected-(U1C-IO_L38P_2-PadN22)") (class "Default")
      (node (ref "U1") (pin "N22") (pinfunction "IO_L38P_2_N22") (pintype "bidirectional"))
    )
    (net (code "543") (name "unconnected-(U1C-IO_L39N_2-PadN23)") (class "Default")
      (node (ref "U1") (pin "N23") (pinfunction "IO_L39N_2_N23") (pintype "bidirectional"))
    )
    (net (code "544") (name "unconnected-(U1C-IO_L40P_2{slash}VREF_2-PadN26)") (class "Default")
      (node (ref "U1") (pin "N26") (pinfunction "IO_L40P_2/VREF_2_N26") (pintype "bidirectional"))
    )
    (net (code "545") (name "unconnected-(U1C-NC-PadF22)") (class "Default")
      (node (ref "U1") (pin "F22") (pinfunction "NC_F22") (pintype "bidirectional+no_connect"))
    )
    (net (code "546") (name "unconnected-(U1D-IO_L01N_3{slash}VRP_3-PadAA22)") (class "Default")
      (node (ref "U1") (pin "AA22") (pinfunction "IO_L01N_3/VRP_3_AA22") (pintype "bidirectional"))
    )
    (net (code "547") (name "unconnected-(U1D-IO_L01P_3{slash}VRN_3-PadAA21)") (class "Default")
      (node (ref "U1") (pin "AA21") (pinfunction "IO_L01P_3/VRN_3_AA21") (pintype "bidirectional"))
    )
    (net (code "548") (name "unconnected-(U1D-IO_L10N_3-PadW21)") (class "Default")
      (node (ref "U1") (pin "W21") (pinfunction "IO_L10N_3_W21") (pintype "bidirectional"))
    )
    (net (code "549") (name "unconnected-(U1D-IO_L10P_3-PadW20)") (class "Default")
      (node (ref "U1") (pin "W20") (pinfunction "IO_L10P_3_W20") (pintype "bidirectional"))
    )
    (net (code "550") (name "unconnected-(U1D-IO_L16N_3-PadV21)") (class "Default")
      (node (ref "U1") (pin "V21") (pinfunction "IO_L16N_3_V21") (pintype "bidirectional"))
    )
    (net (code "551") (name "unconnected-(U1D-IO_L16P_3-PadW22)") (class "Default")
      (node (ref "U1") (pin "W22") (pinfunction "IO_L16P_3_W22") (pintype "bidirectional"))
    )
    (net (code "552") (name "unconnected-(U1D-IO_L20N_3-PadU20)") (class "Default")
      (node (ref "U1") (pin "U20") (pinfunction "IO_L20N_3_U20") (pintype "bidirectional"))
    )
    (net (code "553") (name "unconnected-(U1D-IO_L20P_3-PadV20)") (class "Default")
      (node (ref "U1") (pin "V20") (pinfunction "IO_L20P_3_V20") (pintype "bidirectional"))
    )
    (net (code "554") (name "unconnected-(U1D-IO_L21P_3-PadV22)") (class "Default")
      (node (ref "U1") (pin "V22") (pinfunction "IO_L21P_3_V22") (pintype "bidirectional"))
    )
    (net (code "555") (name "unconnected-(U1D-IO_L23N_3-PadU22)") (class "Default")
      (node (ref "U1") (pin "U22") (pinfunction "IO_L23N_3_U22") (pintype "bidirectional"))
    )
    (net (code "556") (name "unconnected-(U1D-IO_L23P_3{slash}VREF_3-PadU21)") (class "Default")
      (node (ref "U1") (pin "U21") (pinfunction "IO_L23P_3/VREF_3_U21") (pintype "bidirectional"))
    )
    (net (code "557") (name "unconnected-(U1D-IO_L27N_3-PadT20)") (class "Default")
      (node (ref "U1") (pin "T20") (pinfunction "IO_L27N_3_T20") (pintype "bidirectional"))
    )
    (net (code "558") (name "unconnected-(U1D-IO_L28P_3-PadT21)") (class "Default")
      (node (ref "U1") (pin "T21") (pinfunction "IO_L28P_3_T21") (pintype "bidirectional"))
    )
    (net (code "559") (name "unconnected-(U1D-IO_L31N_3-PadR20)") (class "Default")
      (node (ref "U1") (pin "R20") (pinfunction "IO_L31N_3_R20") (pintype "bidirectional"))
    )
    (net (code "560") (name "unconnected-(U1D-IO_L35N_3-PadP20)") (class "Default")
      (node (ref "U1") (pin "P20") (pinfunction "IO_L35N_3_P20") (pintype "bidirectional"))
    )
    (net (code "561") (name "unconnected-(U1E-IO_L01N_4{slash}VRP_4-PadAB22)") (class "Default")
      (node (ref "U1") (pin "AB22") (pinfunction "IO_L01N_4/VRP_4_AB22") (pintype "bidirectional"))
    )
    (net (code "562") (name "unconnected-(U1E-IO_L01P_4{slash}VRN_4-PadAC22)") (class "Default")
      (node (ref "U1") (pin "AC22") (pinfunction "IO_L01P_4/VRN_4_AC22") (pintype "bidirectional"))
    )
    (net (code "563") (name "unconnected-(U1F-IO_L10N_5{slash}VRP_5-PadAF7)") (class "Default")
      (node (ref "U1") (pin "AF7") (pinfunction "IO_L10N_5/VRP_5_AF7") (pintype "bidirectional"))
    )
    (net (code "564") (name "unconnected-(U1F-IO_L10P_5{slash}VRN_5-PadAE7)") (class "Default")
      (node (ref "U1") (pin "AE7") (pinfunction "IO_L10P_5/VRN_5_AE7") (pintype "bidirectional"))
    )
    (net (code "565") (name "unconnected-(U1F-IO_L27P_5-PadW12)") (class "Default")
      (node (ref "U1") (pin "W12") (pinfunction "IO_L27P_5_W12") (pintype "bidirectional"))
    )
    (net (code "566") (name "unconnected-(U1F-IO_L31P_5{slash}D5-PadAB13)") (class "Default")
      (node (ref "U1") (pin "AB13") (pinfunction "IO_L31P_5/D5_AB13") (pintype "bidirectional"))
    )
    (net (code "567") (name "unconnected-(U1G-IO_L01N_6{slash}VRP_6-PadAD2)") (class "Default")
      (node (ref "U1") (pin "AD2") (pinfunction "IO_L01N_6/VRP_6_AD2") (pintype "bidirectional"))
    )
    (net (code "568") (name "unconnected-(U1G-IO_L01P_6{slash}VRN_6-PadAD1)") (class "Default")
      (node (ref "U1") (pin "AD1") (pinfunction "IO_L01P_6/VRN_6_AD1") (pintype "bidirectional"))
    )
    (net (code "569") (name "unconnected-(U1G-IO_L07P_6-PadAA3)") (class "Default")
      (node (ref "U1") (pin "AA3") (pinfunction "IO_L07P_6_AA3") (pintype "bidirectional"))
    )
    (net (code "570") (name "unconnected-(U1G-IO_L08P_6-PadY4)") (class "Default")
      (node (ref "U1") (pin "Y4") (pinfunction "IO_L08P_6_Y4") (pintype "bidirectional"))
    )
    (net (code "571") (name "unconnected-(U1G-IO_L22P_6-PadV2)") (class "Default")
      (node (ref "U1") (pin "V2") (pinfunction "IO_L22P_6_V2") (pintype "bidirectional"))
    )
    (net (code "572") (name "unconnected-(U1G-NC-PadAA5)") (class "Default")
      (node (ref "U1") (pin "AA5") (pinfunction "NC_AA5") (pintype "bidirectional+no_connect"))
    )
    (net (code "573") (name "unconnected-(U1H-IO_L01N_7{slash}VRP_7-PadF5)") (class "Default")
      (node (ref "U1") (pin "F5") (pinfunction "IO_L01N_7/VRP_7_F5") (pintype "bidirectional"))
    )
    (net (code "574") (name "unconnected-(U1H-IO_L01P_7{slash}VRN_7-PadF6)") (class "Default")
      (node (ref "U1") (pin "F6") (pinfunction "IO_L01P_7/VRN_7_F6") (pintype "bidirectional"))
    )
    (net (code "575") (name "unconnected-(U1H-IO_L05N_7-PadG6)") (class "Default")
      (node (ref "U1") (pin "G6") (pinfunction "IO_L05N_7_G6") (pintype "bidirectional"))
    )
    (net (code "576") (name "unconnected-(U1H-IO_L10N_7-PadH6)") (class "Default")
      (node (ref "U1") (pin "H6") (pinfunction "IO_L10N_7_H6") (pintype "bidirectional"))
    )
    (net (code "577") (name "unconnected-(U1H-IO_L16N_7-PadJ6)") (class "Default")
      (node (ref "U1") (pin "J6") (pinfunction "IO_L16N_7_J6") (pintype "bidirectional"))
    )
  )
)
